# SCH_SPEAR.net
KiCad netlist of a schematic drawn in EasyEDA
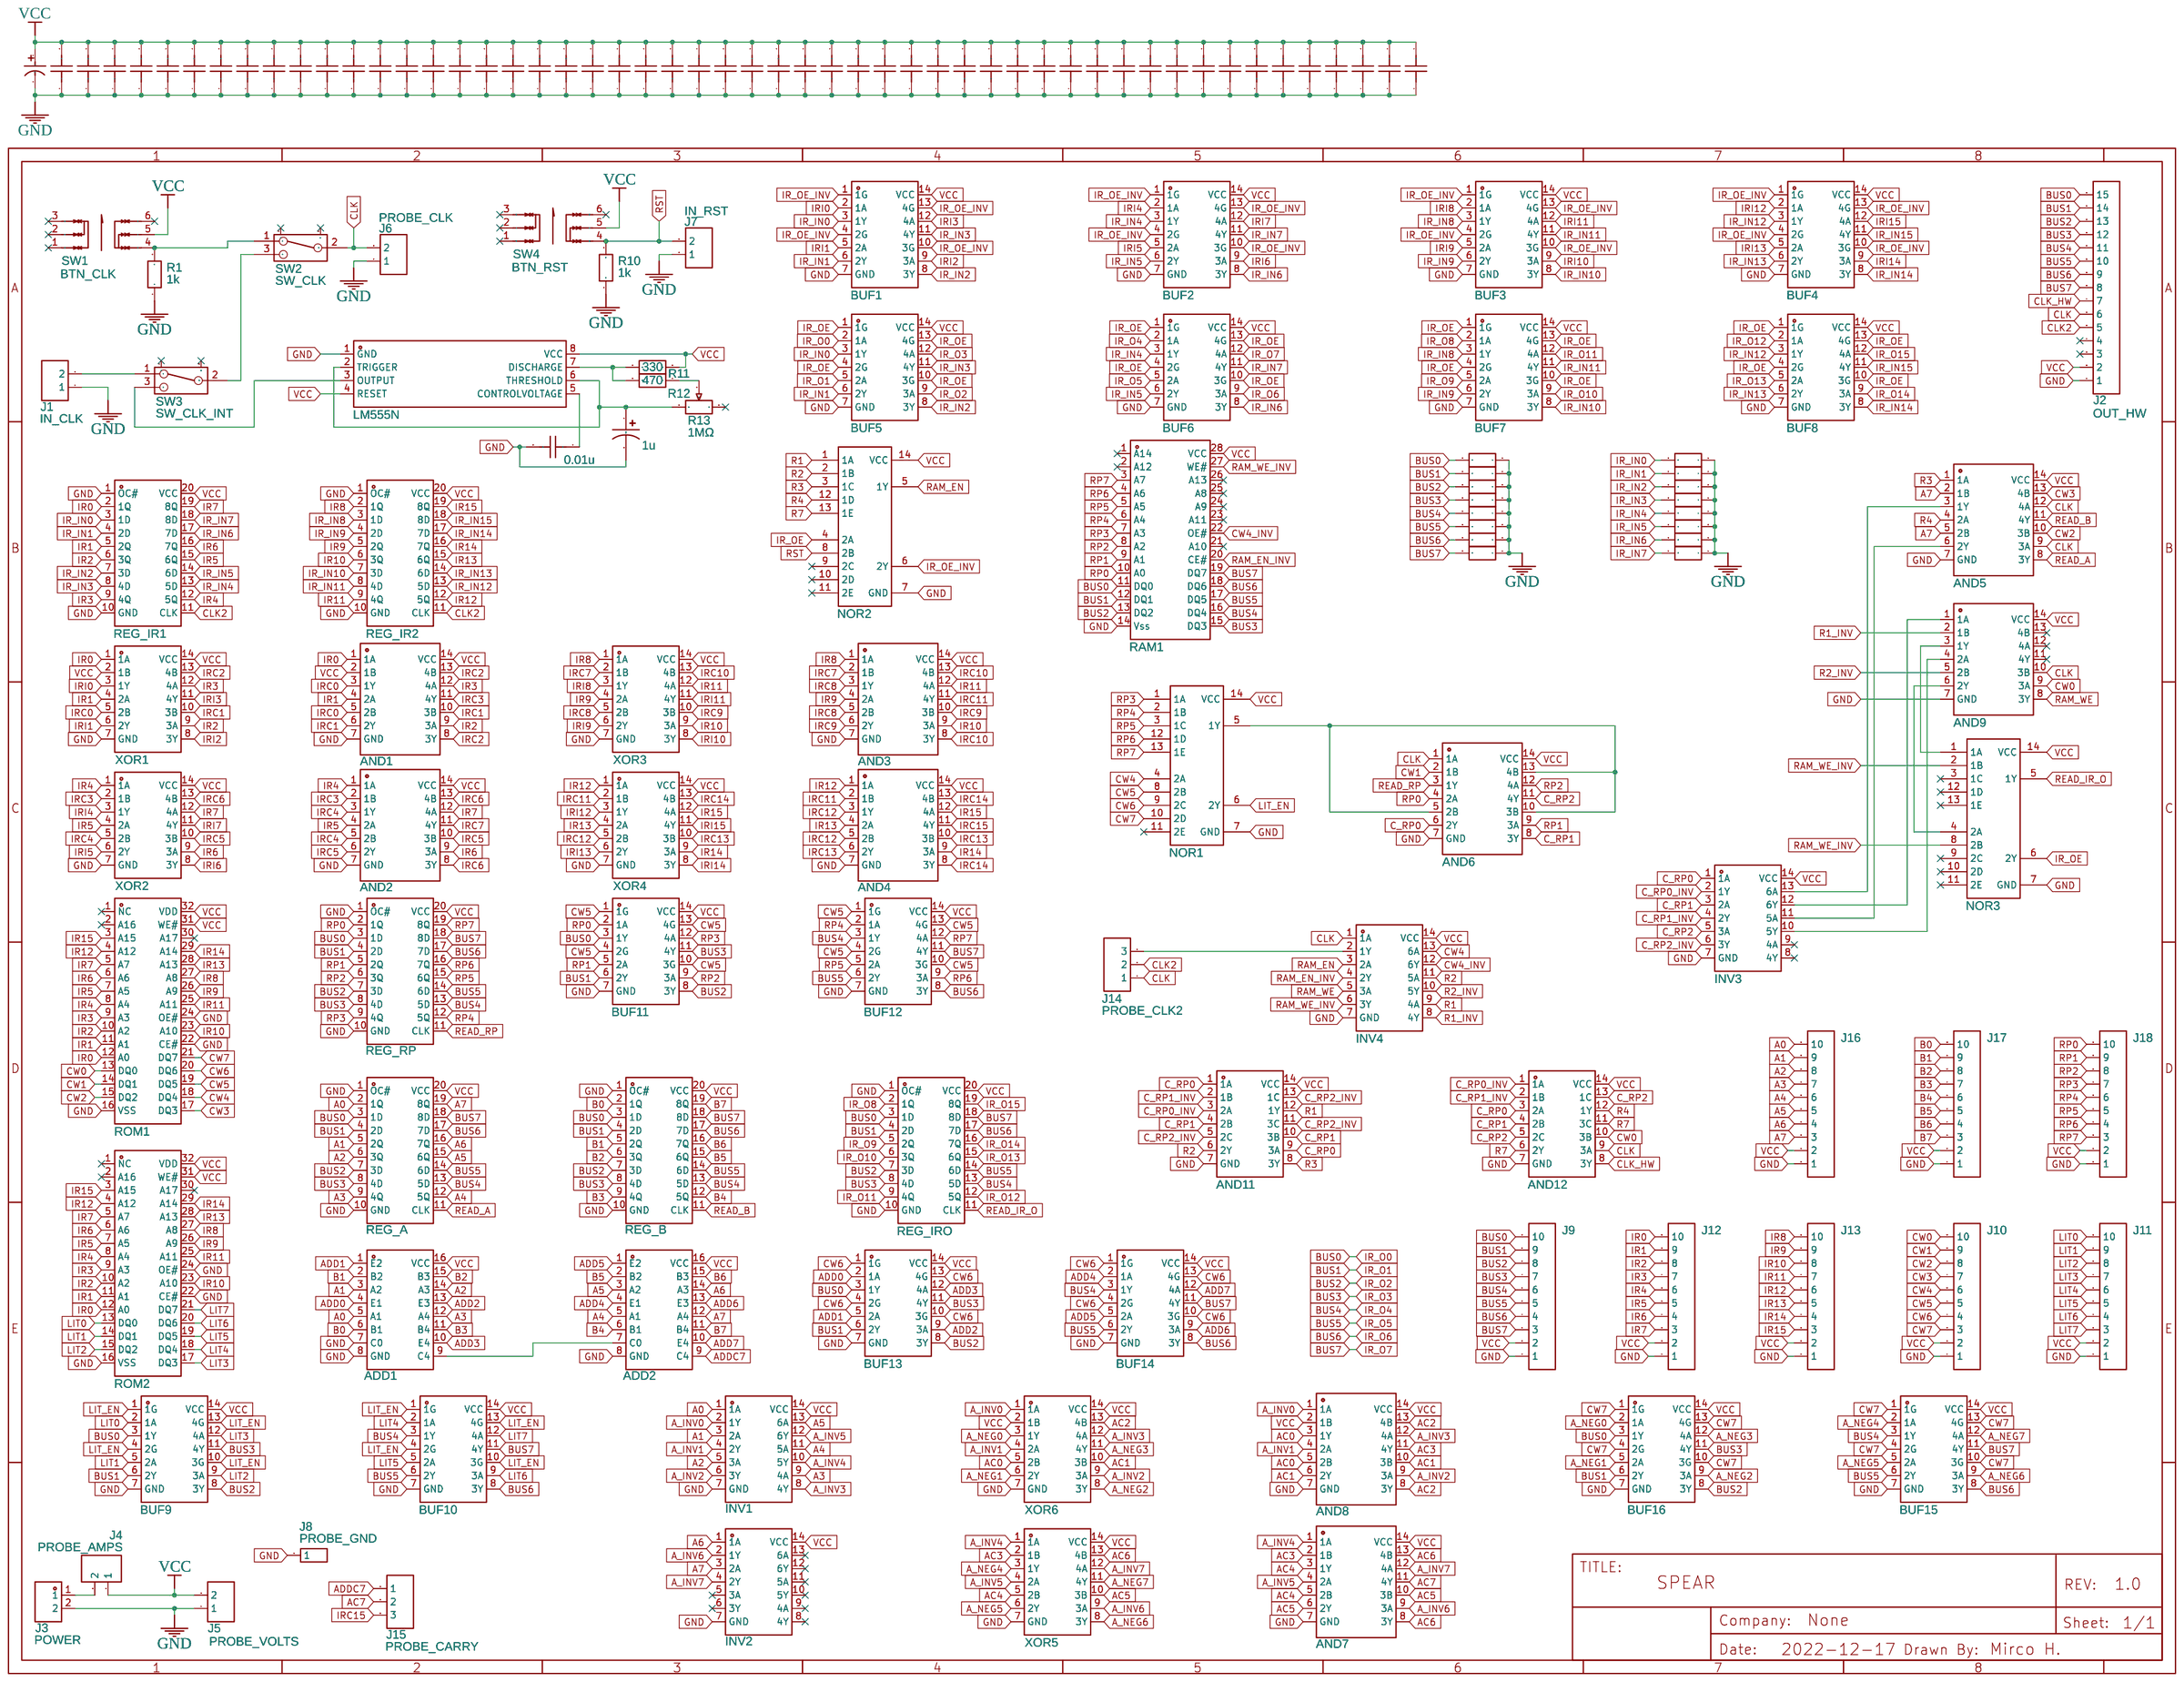
[diagram p0: schematic sheet]

(export (version "E")
  (design (tool "Eeschema 10.0.6"))
  (components
    (comp (ref "ADD1")
      (value "XD74LS283")
      (fields (field (name "BOM_Supplier Part") "C561301"))
      (libsource (lib "") (part "XD74LS283"))
    )
    (comp (ref "ADD2")
      (value "XD74LS283")
      (fields (field (name "BOM_Supplier Part") "C561301"))
      (libsource (lib "") (part "XD74LS283"))
    )
    (comp (ref "AND1")
      (value "SN74LS08DR")
      (fields (field (name "BOM_Supplier Part") "C6802"))
      (libsource (lib "") (part "SN74LS08DR"))
    )
    (comp (ref "AND2")
      (value "SN74LS08DR")
      (fields (field (name "BOM_Supplier Part") "C6802"))
      (libsource (lib "") (part "SN74LS08DR"))
    )
    (comp (ref "AND3")
      (value "SN74LS08DR")
      (fields (field (name "BOM_Supplier Part") "C6802"))
      (libsource (lib "") (part "SN74LS08DR"))
    )
    (comp (ref "AND4")
      (value "SN74LS08DR")
      (fields (field (name "BOM_Supplier Part") "C6802"))
      (libsource (lib "") (part "SN74LS08DR"))
    )
    (comp (ref "AND5")
      (value "SN74LS08DR")
      (fields (field (name "BOM_Supplier Part") "C6802"))
      (libsource (lib "") (part "SN74LS08DR"))
    )
    (comp (ref "AND6")
      (value "SN74LS08DR")
      (fields (field (name "BOM_Supplier Part") "C6802"))
      (libsource (lib "") (part "SN74LS08DR"))
    )
    (comp (ref "AND7")
      (value "SN74LS08DR")
      (fields (field (name "BOM_Supplier Part") "C6802"))
      (libsource (lib "") (part "SN74LS08DR"))
    )
    (comp (ref "AND8")
      (value "SN74LS08DR")
      (fields (field (name "BOM_Supplier Part") "C6802"))
      (libsource (lib "") (part "SN74LS08DR"))
    )
    (comp (ref "AND9")
      (value "SN74LS08DR")
      (fields (field (name "BOM_Supplier Part") "C6802"))
      (libsource (lib "") (part "SN74LS08DR"))
    )
    (comp (ref "AND11")
      (value "XL74LS11")
      (fields (field (name "BOM_Supplier Part") "C521168"))
      (libsource (lib "") (part "XL74LS11"))
    )
    (comp (ref "AND12")
      (value "XL74LS11")
      (fields (field (name "BOM_Supplier Part") "C521168"))
      (libsource (lib "") (part "XL74LS11"))
    )
    (comp (ref "BUF1")
      (value "SN74LS126ADR")
      (fields (field (name "BOM_Supplier Part") "C2865257"))
      (libsource (lib "") (part "SN74LS126ADR"))
    )
    (comp (ref "BUF2")
      (value "SN74LS126ADR")
      (fields (field (name "BOM_Supplier Part") "C2865257"))
      (libsource (lib "") (part "SN74LS126ADR"))
    )
    (comp (ref "BUF3")
      (value "SN74LS126ADR")
      (fields (field (name "BOM_Supplier Part") "C2865257"))
      (libsource (lib "") (part "SN74LS126ADR"))
    )
    (comp (ref "BUF4")
      (value "SN74LS126ADR")
      (fields (field (name "BOM_Supplier Part") "C2865257"))
      (libsource (lib "") (part "SN74LS126ADR"))
    )
    (comp (ref "BUF5")
      (value "SN74LS126ADR")
      (fields (field (name "BOM_Supplier Part") "C2865257"))
      (libsource (lib "") (part "SN74LS126ADR"))
    )
    (comp (ref "BUF6")
      (value "SN74LS126ADR")
      (fields (field (name "BOM_Supplier Part") "C2865257"))
      (libsource (lib "") (part "SN74LS126ADR"))
    )
    (comp (ref "BUF7")
      (value "SN74LS126ADR")
      (fields (field (name "BOM_Supplier Part") "C2865257"))
      (libsource (lib "") (part "SN74LS126ADR"))
    )
    (comp (ref "BUF8")
      (value "SN74LS126ADR")
      (fields (field (name "BOM_Supplier Part") "C2865257"))
      (libsource (lib "") (part "SN74LS126ADR"))
    )
    (comp (ref "BUF9")
      (value "SN74LS126ADR")
      (fields (field (name "BOM_Supplier Part") "C2865257"))
      (libsource (lib "") (part "SN74LS126ADR"))
    )
    (comp (ref "BUF10")
      (value "SN74LS126ADR")
      (fields (field (name "BOM_Supplier Part") "C2865257"))
      (libsource (lib "") (part "SN74LS126ADR"))
    )
    (comp (ref "BUF11")
      (value "SN74LS126ADR")
      (fields (field (name "BOM_Supplier Part") "C2865257"))
      (libsource (lib "") (part "SN74LS126ADR"))
    )
    (comp (ref "BUF12")
      (value "SN74LS126ADR")
      (fields (field (name "BOM_Supplier Part") "C2865257"))
      (libsource (lib "") (part "SN74LS126ADR"))
    )
    (comp (ref "BUF13")
      (value "SN74LS126ADR")
      (fields (field (name "BOM_Supplier Part") "C2865257"))
      (libsource (lib "") (part "SN74LS126ADR"))
    )
    (comp (ref "BUF14")
      (value "SN74LS126ADR")
      (fields (field (name "BOM_Supplier Part") "C2865257"))
      (libsource (lib "") (part "SN74LS126ADR"))
    )
    (comp (ref "BUF15")
      (value "SN74LS126ADR")
      (fields (field (name "BOM_Supplier Part") "C2865257"))
      (libsource (lib "") (part "SN74LS126ADR"))
    )
    (comp (ref "BUF16")
      (value "SN74LS126ADR")
      (fields (field (name "BOM_Supplier Part") "C2865257"))
      (libsource (lib "") (part "SN74LS126ADR"))
    )
    (comp (ref "C1") (value "0.1u") (libsource (lib "") (part "C_0603_US")))
    (comp (ref "C2") (value "0.01u") (libsource (lib "") (part "C_0603_US_1")))
    (comp (ref "C3") (value "1u") (libsource (lib "") (part "C_Tan_SMD_A_US")))
    (comp (ref "C4") (value "0.1u") (libsource (lib "") (part "C_0603_US")))
    (comp (ref "C5") (value "0.1u") (libsource (lib "") (part "C_0603_US")))
    (comp (ref "C6") (value "0.1u") (libsource (lib "") (part "C_0603_US")))
    (comp (ref "C7") (value "0.1u") (libsource (lib "") (part "C_0603_US")))
    (comp (ref "C8") (value "0.1u") (libsource (lib "") (part "C_0603_US")))
    (comp (ref "C9") (value "0.1u") (libsource (lib "") (part "C_0603_US")))
    (comp (ref "C10") (value "0.1u") (libsource (lib "") (part "C_0603_US")))
    (comp (ref "C11") (value "0.1u") (libsource (lib "") (part "C_0603_US")))
    (comp (ref "C12") (value "0.1u") (libsource (lib "") (part "C_0603_US")))
    (comp (ref "C13") (value "0.1u") (libsource (lib "") (part "C_0603_US")))
    (comp (ref "C14") (value "0.1u") (libsource (lib "") (part "C_0603_US")))
    (comp (ref "C15")
      (value "1000uF")
      (fields
        (field (name "BOM_Manufacturer Part") "KM108M025G17RR0VH2FP0")
        (field (name "BOM_Supplier Part") "C10750")
      )
      (libsource (lib "") (part "1000uF 25V"))
    )
    (comp (ref "C58") (value "0.1u") (libsource (lib "") (part "C_0603_US")))
    (comp (ref "C59") (value "0.1u") (libsource (lib "") (part "C_0603_US")))
    (comp (ref "C60") (value "0.1u") (libsource (lib "") (part "C_0603_US")))
    (comp (ref "C61") (value "0.1u") (libsource (lib "") (part "C_0603_US")))
    (comp (ref "C62") (value "0.1u") (libsource (lib "") (part "C_0603_US")))
    (comp (ref "C63") (value "0.1u") (libsource (lib "") (part "C_0603_US")))
    (comp (ref "C64") (value "0.1u") (libsource (lib "") (part "C_0603_US")))
    (comp (ref "C70") (value "0.1u") (libsource (lib "") (part "C_0603_US")))
    (comp (ref "C71") (value "0.1u") (libsource (lib "") (part "C_0603_US")))
    (comp (ref "C72") (value "0.1u") (libsource (lib "") (part "C_0603_US")))
    (comp (ref "C73") (value "0.1u") (libsource (lib "") (part "C_0603_US")))
    (comp (ref "C74") (value "0.1u") (libsource (lib "") (part "C_0603_US")))
    (comp (ref "C75") (value "0.1u") (libsource (lib "") (part "C_0603_US")))
    (comp (ref "C76") (value "0.1u") (libsource (lib "") (part "C_0603_US")))
    (comp (ref "C77") (value "0.1u") (libsource (lib "") (part "C_0603_US")))
    (comp (ref "C78") (value "0.1u") (libsource (lib "") (part "C_0603_US")))
    (comp (ref "C79") (value "0.1u") (libsource (lib "") (part "C_0603_US")))
    (comp (ref "C85") (value "0.1u") (libsource (lib "") (part "C_0603_US")))
    (comp (ref "C86") (value "0.1u") (libsource (lib "") (part "C_0603_US")))
    (comp (ref "C87") (value "0.1u") (libsource (lib "") (part "C_0603_US")))
    (comp (ref "C88") (value "0.1u") (libsource (lib "") (part "C_0603_US")))
    (comp (ref "C89") (value "0.1u") (libsource (lib "") (part "C_0603_US")))
    (comp (ref "C90") (value "0.1u") (libsource (lib "") (part "C_0603_US")))
    (comp (ref "C91") (value "0.1u") (libsource (lib "") (part "C_0603_US")))
    (comp (ref "C92") (value "0.1u") (libsource (lib "") (part "C_0603_US")))
    (comp (ref "C93") (value "0.1u") (libsource (lib "") (part "C_0603_US")))
    (comp (ref "C94") (value "0.1u") (libsource (lib "") (part "C_0603_US")))
    (comp (ref "C95") (value "0.1u") (libsource (lib "") (part "C_0603_US")))
    (comp (ref "C96") (value "0.1u") (libsource (lib "") (part "C_0603_US")))
    (comp (ref "C102") (value "0.1u") (libsource (lib "") (part "C_0603_US")))
    (comp (ref "C103") (value "0.1u") (libsource (lib "") (part "C_0603_US")))
    (comp (ref "C104") (value "0.1u") (libsource (lib "") (part "C_0603_US")))
    (comp (ref "C105") (value "0.1u") (libsource (lib "") (part "C_0603_US")))
    (comp (ref "C106") (value "0.1u") (libsource (lib "") (part "C_0603_US")))
    (comp (ref "C107") (value "0.1u") (libsource (lib "") (part "C_0603_US")))
    (comp (ref "C108") (value "0.1u") (libsource (lib "") (part "C_0603_US")))
    (comp (ref "C109") (value "0.1u") (libsource (lib "") (part "C_0603_US")))
    (comp (ref "C110") (value "0.1u") (libsource (lib "") (part "C_0603_US")))
    (comp (ref "C111") (value "0.1u") (libsource (lib "") (part "C_0603_US")))
    (comp (ref "C112") (value "0.1u") (libsource (lib "") (part "C_0603_US")))
    (comp (ref "INV1")
      (value "XL74LS04")
      (fields (field (name "BOM_Supplier Part") "C513511"))
      (libsource (lib "") (part "XL74LS04"))
    )
    (comp (ref "INV2")
      (value "XL74LS04")
      (fields (field (name "BOM_Supplier Part") "C513511"))
      (libsource (lib "") (part "XL74LS04"))
    )
    (comp (ref "INV3")
      (value "XL74LS04")
      (fields (field (name "BOM_Supplier Part") "C513511"))
      (libsource (lib "") (part "XL74LS04"))
    )
    (comp (ref "INV4")
      (value "XL74LS04")
      (fields (field (name "BOM_Supplier Part") "C513511"))
      (libsource (lib "") (part "XL74LS04"))
    )
    (comp (ref "J1")
      (value "IN_CLK")
      (fields (field (name "BOM_Supplier Part") "C124375"))
      (libsource (lib "") (part "HDR-M-2.54_1x2_2"))
    )
    (comp (ref "J2")
      (value "OUT_HW")
      (fields (field (name "BOM_Supplier Part") "C124373"))
      (libsource (lib "") (part "HDR-M-2.54_1x15"))
    )
    (comp (ref "J3")
      (value "POWER")
      (fields
        (field (name "BOM_Manufacturer Part") "DB126V-5.0-2P-GN-P")
        (field (name "BOM_Supplier Part") "C395849")
      )
      (libsource (lib "") (part "DB126V-5.0-2P"))
    )
    (comp (ref "J4")
      (value "PROBE_AMPS")
      (fields (field (name "BOM_Supplier Part") "C124375"))
      (libsource (lib "") (part "HDR-M-2.54_1x2_1"))
    )
    (comp (ref "J5")
      (value "PROBE_VOLTS")
      (fields (field (name "BOM_Supplier Part") "C124375"))
      (libsource (lib "") (part "HDR-M-2.54_1x2"))
    )
    (comp (ref "J6")
      (value "PROBE_CLK")
      (fields (field (name "BOM_Supplier Part") "C124375"))
      (libsource (lib "") (part "HDR-M-2.54_1x2"))
    )
    (comp (ref "J7")
      (value "IN_RST")
      (fields (field (name "BOM_Supplier Part") "C124375"))
      (libsource (lib "") (part "HDR-M-2.54_1x2"))
    )
    (comp (ref "J8")
      (value "PROBE_GND")
      (fields (field (name "BOM_Supplier Part") "C81276"))
      (libsource (lib "") (part "HDR-M-2.54_1x1"))
    )
    (comp (ref "J9")
      (value "PROBE_BUS")
      (fields (field (name "BOM_Supplier Part") "C57369"))
      (libsource (lib "") (part "HDR-M-2.54_1x10"))
    )
    (comp (ref "J10")
      (value "PROBE_CW")
      (fields (field (name "BOM_Supplier Part") "C57369"))
      (libsource (lib "") (part "HDR-M-2.54_1x10"))
    )
    (comp (ref "J11")
      (value "PROBE_LIT")
      (fields (field (name "BOM_Supplier Part") "C57369"))
      (libsource (lib "") (part "HDR-M-2.54_1x10"))
    )
    (comp (ref "J12")
      (value "PROBE_IR1")
      (fields (field (name "BOM_Supplier Part") "C57369"))
      (libsource (lib "") (part "HDR-M-2.54_1x10"))
    )
    (comp (ref "J13")
      (value "PROBE_IR2")
      (fields (field (name "BOM_Supplier Part") "C57369"))
      (libsource (lib "") (part "HDR-M-2.54_1x10"))
    )
    (comp (ref "J14")
      (value "PROBE_CLK2")
      (fields (field (name "BOM_Supplier Part") "C180248"))
      (libsource (lib "") (part "HDR-M-2.54_1x3"))
    )
    (comp (ref "J15")
      (value "PROBE_CARRY")
      (fields (field (name "BOM_Supplier Part") "C180248"))
      (libsource (lib "") (part "HDR-M-2.54_1x3_1"))
    )
    (comp (ref "J16")
      (value "PROBE_A")
      (fields (field (name "BOM_Supplier Part") "C57369"))
      (libsource (lib "") (part "HDR-M-2.54_1x10"))
    )
    (comp (ref "J17")
      (value "PROBE_B")
      (fields (field (name "BOM_Supplier Part") "C57369"))
      (libsource (lib "") (part "HDR-M-2.54_1x10"))
    )
    (comp (ref "J18")
      (value "PROBE_RP")
      (fields (field (name "BOM_Supplier Part") "C57369"))
      (libsource (lib "") (part "HDR-M-2.54_1x10"))
    )
    (comp (ref "NOR1") (value "LISA_CPU_74LS260") (libsource (lib "") (part "LISA_CPU_74LS260")))
    (comp (ref "NOR2") (value "LISA_CPU_74LS260") (libsource (lib "") (part "LISA_CPU_74LS260")))
    (comp (ref "NOR3") (value "LISA_CPU_74LS260") (libsource (lib "") (part "LISA_CPU_74LS260")))
    (comp (ref "R1") (value "1k") (libsource (lib "") (part "R_0603_EU_1")))
    (comp (ref "R2") (value "10k") (libsource (lib "") (part "R_0603_EU")))
    (comp (ref "R3") (value "10k") (libsource (lib "") (part "R_0603_EU")))
    (comp (ref "R4") (value "10k") (libsource (lib "") (part "R_0603_EU")))
    (comp (ref "R5") (value "10k") (libsource (lib "") (part "R_0603_EU")))
    (comp (ref "R6") (value "10k") (libsource (lib "") (part "R_0603_EU")))
    (comp (ref "R7") (value "10k") (libsource (lib "") (part "R_0603_EU")))
    (comp (ref "R8") (value "10k") (libsource (lib "") (part "R_0603_EU")))
    (comp (ref "R9") (value "10k") (libsource (lib "") (part "R_0603_EU")))
    (comp (ref "R10") (value "1k") (libsource (lib "") (part "R_0603_EU_1")))
    (comp (ref "R11") (value "330") (libsource (lib "") (part "R_0603_EU")))
    (comp (ref "R12") (value "470") (libsource (lib "") (part "R_0603_EU")))
    (comp (ref "R13")
      (value "1MΩ")
      (fields
        (field (name "BOM_Manufacturer Part") "3362P-1-105")
        (field (name "BOM_Supplier Part") "C118945")
      )
      (libsource (lib "") (part "3362P-1-105_C118945"))
    )
    (comp (ref "R14") (value "10k") (libsource (lib "") (part "R_0603_EU")))
    (comp (ref "R15") (value "10k") (libsource (lib "") (part "R_0603_EU")))
    (comp (ref "R16") (value "10k") (libsource (lib "") (part "R_0603_EU")))
    (comp (ref "R17") (value "10k") (libsource (lib "") (part "R_0603_EU")))
    (comp (ref "R18") (value "10k") (libsource (lib "") (part "R_0603_EU")))
    (comp (ref "R19") (value "10k") (libsource (lib "") (part "R_0603_EU")))
    (comp (ref "R20") (value "10k") (libsource (lib "") (part "R_0603_EU")))
    (comp (ref "R21") (value "10k") (libsource (lib "") (part "R_0603_EU")))
    (comp (ref "RAM1")
      (value "LY62256SL-70LL")
      (fields (field (name "BOM_Supplier Part") "C261867"))
      (libsource (lib "") (part "LY62256SL-70LL"))
    )
    (comp (ref "REG1")
      (value "REG_IR1")
      (fields
        (field (name "BOM_Manufacturer Part") "SN74LS374NSR")
        (field (name "BOM_Supplier Part") "C7764")
      )
      (libsource (lib "") (part "SN74LS374NSR"))
    )
    (comp (ref "REG2")
      (value "REG_IR2")
      (fields
        (field (name "BOM_Manufacturer Part") "SN74LS374NSR")
        (field (name "BOM_Supplier Part") "C7764")
      )
      (libsource (lib "") (part "SN74LS374NSR"))
    )
    (comp (ref "REG_A")
      (value "SN74LS374NSR")
      (fields (field (name "BOM_Supplier Part") "C7764"))
      (libsource (lib "") (part "SN74LS374NSR_2"))
    )
    (comp (ref "REG_B")
      (value "SN74LS374NSR")
      (fields (field (name "BOM_Supplier Part") "C7764"))
      (libsource (lib "") (part "SN74LS374NSR_4"))
    )
    (comp (ref "REG_IRO")
      (value "SN74LS374NSR")
      (fields (field (name "BOM_Supplier Part") "C7764"))
      (libsource (lib "") (part "SN74LS374NSR_1"))
    )
    (comp (ref "REG_RP")
      (value "SN74LS374NSR")
      (fields (field (name "BOM_Supplier Part") "C7764"))
      (libsource (lib "") (part "SN74LS374NSR_3"))
    )
    (comp (ref "ROM1")
      (value "SST39SF020A-70-4I-NHE")
      (fields (field (name "BOM_Supplier Part") "C645934"))
      (libsource (lib "") (part "SST39SF020A-70-4I-NHE"))
    )
    (comp (ref "ROM2")
      (value "SST39SF020A-70-4I-NHE")
      (fields (field (name "BOM_Supplier Part") "C645934"))
      (libsource (lib "") (part "SST39SF020A-70-4I-NHE"))
    )
    (comp (ref "SW1")
      (value "BTN_CLK")
      (fields (field (name "BOM_Manufacturer Part") "XKB8080-W") (field (name "BOM_Supplier Part") "C318861"))
      (libsource (lib "") (part "XKB8080-W"))
    )
    (comp (ref "SW2")
      (value "SW_CLK")
      (fields
        (field (name "BOM_Manufacturer Part") "SK-12E12-G5")
        (field (name "BOM_Supplier Part") "C136720")
      )
      (libsource (lib "") (part "SK-12E12-G5"))
    )
    (comp (ref "SW3")
      (value "SW_CLK_INT")
      (fields
        (field (name "BOM_Manufacturer Part") "SK-12E12-G5")
        (field (name "BOM_Supplier Part") "C136720")
      )
      (libsource (lib "") (part "SK-12E12-G5"))
    )
    (comp (ref "SW4")
      (value "BTN_RST")
      (fields (field (name "BOM_Manufacturer Part") "XKB8080-W") (field (name "BOM_Supplier Part") "C318861"))
      (libsource (lib "") (part "XKB8080-W"))
    )
    (comp (ref "U1")
      (value "LM555N")
      (fields (field (name "BOM_Supplier Part") "C725327"))
      (libsource (lib "") (part "LM555N"))
    )
    (comp (ref "XOR1")
      (value "XD74LS86")
      (fields (field (name "BOM_Supplier Part") "C556290"))
      (libsource (lib "") (part "XD74LS86"))
    )
    (comp (ref "XOR2")
      (value "XD74LS86")
      (fields (field (name "BOM_Supplier Part") "C556290"))
      (libsource (lib "") (part "XD74LS86"))
    )
    (comp (ref "XOR3")
      (value "XD74LS86")
      (fields (field (name "BOM_Supplier Part") "C556290"))
      (libsource (lib "") (part "XD74LS86"))
    )
    (comp (ref "XOR4")
      (value "XD74LS86")
      (fields (field (name "BOM_Supplier Part") "C556290"))
      (libsource (lib "") (part "XD74LS86"))
    )
    (comp (ref "XOR5")
      (value "XD74LS86")
      (fields (field (name "BOM_Supplier Part") "C556290"))
      (libsource (lib "") (part "XD74LS86"))
    )
    (comp (ref "XOR6")
      (value "XD74LS86")
      (fields (field (name "BOM_Supplier Part") "C556290"))
      (libsource (lib "") (part "XD74LS86"))
    )
  )
  (nets
    (net (code "1") (name "A0") (class "Default")
      (node (ref "ADD1") (pin "5") (pinfunction "A1_5") (pintype "unspecified"))
      (node (ref "INV1") (pin "1") (pinfunction "1A_1") (pintype "unspecified"))
      (node (ref "J16") (pin "10") (pinfunction "10_10") (pintype "unspecified"))
      (node (ref "REG_A") (pin "2") (pinfunction "1Q_2") (pintype "unspecified"))
    )
    (net (code "2") (name "A1") (class "Default")
      (node (ref "ADD1") (pin "3") (pinfunction "A2_3") (pintype "unspecified"))
      (node (ref "INV1") (pin "3") (pinfunction "2A_3") (pintype "unspecified"))
      (node (ref "J16") (pin "9") (pinfunction "9_9") (pintype "unspecified"))
      (node (ref "REG_A") (pin "5") (pinfunction "2Q_5") (pintype "unspecified"))
    )
    (net (code "3") (name "A2") (class "Default")
      (node (ref "ADD1") (pin "14") (pinfunction "A3_14") (pintype "unspecified"))
      (node (ref "INV1") (pin "5") (pinfunction "3A_5") (pintype "unspecified"))
      (node (ref "J16") (pin "8") (pinfunction "8_8") (pintype "unspecified"))
      (node (ref "REG_A") (pin "6") (pinfunction "3Q_6") (pintype "unspecified"))
    )
    (net (code "4") (name "A3") (class "Default")
      (node (ref "ADD1") (pin "12") (pinfunction "A4_12") (pintype "unspecified"))
      (node (ref "INV1") (pin "9") (pinfunction "4A_9") (pintype "unspecified"))
      (node (ref "J16") (pin "7") (pinfunction "7_7") (pintype "unspecified"))
      (node (ref "REG_A") (pin "9") (pinfunction "4Q_9") (pintype "unspecified"))
    )
    (net (code "5") (name "A4") (class "Default")
      (node (ref "ADD2") (pin "5") (pinfunction "A1_5") (pintype "unspecified"))
      (node (ref "INV1") (pin "11") (pinfunction "5A_11") (pintype "unspecified"))
      (node (ref "J16") (pin "6") (pinfunction "6_6") (pintype "unspecified"))
      (node (ref "REG_A") (pin "12") (pinfunction "5Q_12") (pintype "unspecified"))
    )
    (net (code "6") (name "A5") (class "Default")
      (node (ref "ADD2") (pin "3") (pinfunction "A2_3") (pintype "unspecified"))
      (node (ref "INV1") (pin "13") (pinfunction "6A_13") (pintype "unspecified"))
      (node (ref "J16") (pin "5") (pinfunction "5_5") (pintype "unspecified"))
      (node (ref "REG_A") (pin "15") (pinfunction "6Q_15") (pintype "unspecified"))
    )
    (net (code "7") (name "A6") (class "Default")
      (node (ref "ADD2") (pin "14") (pinfunction "A3_14") (pintype "unspecified"))
      (node (ref "INV2") (pin "1") (pinfunction "1A_1") (pintype "unspecified"))
      (node (ref "J16") (pin "4") (pinfunction "4_4") (pintype "unspecified"))
      (node (ref "REG_A") (pin "16") (pinfunction "7Q_16") (pintype "unspecified"))
    )
    (net (code "8") (name "A7") (class "Default")
      (node (ref "ADD2") (pin "12") (pinfunction "A4_12") (pintype "unspecified"))
      (node (ref "AND5") (pin "2") (pinfunction "1B_2") (pintype "unspecified"))
      (node (ref "AND5") (pin "5") (pinfunction "2B_5") (pintype "unspecified"))
      (node (ref "INV2") (pin "3") (pinfunction "2A_3") (pintype "unspecified"))
      (node (ref "J16") (pin "3") (pinfunction "3_3") (pintype "unspecified"))
      (node (ref "REG_A") (pin "19") (pinfunction "8Q_19") (pintype "unspecified"))
    )
    (net (code "9") (name "AC0") (class "Default")
      (node (ref "AND8") (pin "3") (pinfunction "1Y_3") (pintype "unspecified"))
      (node (ref "AND8") (pin "5") (pinfunction "2B_5") (pintype "unspecified"))
      (node (ref "XOR6") (pin "5") (pinfunction "2B_5") (pintype "unspecified"))
    )
    (net (code "10") (name "AC1") (class "Default")
      (node (ref "AND8") (pin "10") (pinfunction "3B_10") (pintype "unspecified"))
      (node (ref "AND8") (pin "6") (pinfunction "2Y_6") (pintype "unspecified"))
      (node (ref "XOR6") (pin "10") (pinfunction "3B_10") (pintype "unspecified"))
    )
    (net (code "11") (name "AC2") (class "Default")
      (node (ref "AND8") (pin "13") (pinfunction "4B_13") (pintype "unspecified"))
      (node (ref "AND8") (pin "8") (pinfunction "3Y_8") (pintype "unspecified"))
      (node (ref "XOR6") (pin "13") (pinfunction "4B_13") (pintype "unspecified"))
    )
    (net (code "12") (name "AC3") (class "Default")
      (node (ref "AND7") (pin "2") (pinfunction "1B_2") (pintype "unspecified"))
      (node (ref "AND8") (pin "11") (pinfunction "4Y_11") (pintype "unspecified"))
      (node (ref "XOR5") (pin "2") (pinfunction "1B_2") (pintype "unspecified"))
    )
    (net (code "13") (name "AC4") (class "Default")
      (node (ref "AND7") (pin "3") (pinfunction "1Y_3") (pintype "unspecified"))
      (node (ref "AND7") (pin "5") (pinfunction "2B_5") (pintype "unspecified"))
      (node (ref "XOR5") (pin "5") (pinfunction "2B_5") (pintype "unspecified"))
    )
    (net (code "14") (name "AC5") (class "Default")
      (node (ref "AND7") (pin "10") (pinfunction "3B_10") (pintype "unspecified"))
      (node (ref "AND7") (pin "6") (pinfunction "2Y_6") (pintype "unspecified"))
      (node (ref "XOR5") (pin "10") (pinfunction "3B_10") (pintype "unspecified"))
    )
    (net (code "15") (name "AC6") (class "Default")
      (node (ref "AND7") (pin "13") (pinfunction "4B_13") (pintype "unspecified"))
      (node (ref "AND7") (pin "8") (pinfunction "3Y_8") (pintype "unspecified"))
      (node (ref "XOR5") (pin "13") (pinfunction "4B_13") (pintype "unspecified"))
    )
    (net (code "16") (name "AC7") (class "Default")
      (node (ref "AND7") (pin "11") (pinfunction "4Y_11") (pintype "unspecified"))
      (node (ref "J15") (pin "2") (pinfunction "2_2") (pintype "input"))
    )
    (net (code "17") (name "ADD0") (class "Default")
      (node (ref "ADD1") (pin "4") (pinfunction "E1_4") (pintype "unspecified"))
      (node (ref "BUF13") (pin "2") (pinfunction "1A_2") (pintype "unspecified"))
    )
    (net (code "18") (name "ADD1") (class "Default")
      (node (ref "ADD1") (pin "1") (pinfunction "E2_1") (pintype "unspecified"))
      (node (ref "BUF13") (pin "5") (pinfunction "2A_5") (pintype "unspecified"))
    )
    (net (code "19") (name "ADD2") (class "Default")
      (node (ref "ADD1") (pin "13") (pinfunction "E3_13") (pintype "unspecified"))
      (node (ref "BUF13") (pin "9") (pinfunction "3A_9") (pintype "unspecified"))
    )
    (net (code "20") (name "ADD3") (class "Default")
      (node (ref "ADD1") (pin "10") (pinfunction "E4_10") (pintype "unspecified"))
      (node (ref "BUF13") (pin "12") (pinfunction "4A_12") (pintype "unspecified"))
    )
    (net (code "21") (name "ADD4") (class "Default")
      (node (ref "ADD2") (pin "4") (pinfunction "E1_4") (pintype "unspecified"))
      (node (ref "BUF14") (pin "2") (pinfunction "1A_2") (pintype "unspecified"))
    )
    (net (code "22") (name "ADD5") (class "Default")
      (node (ref "ADD2") (pin "1") (pinfunction "E2_1") (pintype "unspecified"))
      (node (ref "BUF14") (pin "5") (pinfunction "2A_5") (pintype "unspecified"))
    )
    (net (code "23") (name "ADD6") (class "Default")
      (node (ref "ADD2") (pin "13") (pinfunction "E3_13") (pintype "unspecified"))
      (node (ref "BUF14") (pin "9") (pinfunction "3A_9") (pintype "unspecified"))
    )
    (net (code "24") (name "ADD7") (class "Default")
      (node (ref "ADD2") (pin "10") (pinfunction "E4_10") (pintype "unspecified"))
      (node (ref "BUF14") (pin "12") (pinfunction "4A_12") (pintype "unspecified"))
    )
    (net (code "25") (name "ADDC7") (class "Default")
      (node (ref "ADD2") (pin "9") (pinfunction "C4_9") (pintype "unspecified"))
      (node (ref "J15") (pin "1") (pinfunction "1_1") (pintype "input"))
    )
    (net (code "26") (name "A_INV0") (class "Default")
      (node (ref "AND8") (pin "1") (pinfunction "1A_1") (pintype "unspecified"))
      (node (ref "INV1") (pin "2") (pinfunction "1Y_2") (pintype "unspecified"))
      (node (ref "XOR6") (pin "1") (pinfunction "1A_1") (pintype "unspecified"))
    )
    (net (code "27") (name "A_INV1") (class "Default")
      (node (ref "AND8") (pin "4") (pinfunction "2A_4") (pintype "unspecified"))
      (node (ref "INV1") (pin "4") (pinfunction "2Y_4") (pintype "unspecified"))
      (node (ref "XOR6") (pin "4") (pinfunction "2A_4") (pintype "unspecified"))
    )
    (net (code "28") (name "A_INV2") (class "Default")
      (node (ref "AND8") (pin "9") (pinfunction "3A_9") (pintype "unspecified"))
      (node (ref "INV1") (pin "6") (pinfunction "3Y_6") (pintype "unspecified"))
      (node (ref "XOR6") (pin "9") (pinfunction "3A_9") (pintype "unspecified"))
    )
    (net (code "29") (name "A_INV3") (class "Default")
      (node (ref "AND8") (pin "12") (pinfunction "4A_12") (pintype "unspecified"))
      (node (ref "INV1") (pin "8") (pinfunction "4Y_8") (pintype "unspecified"))
      (node (ref "XOR6") (pin "12") (pinfunction "4A_12") (pintype "unspecified"))
    )
    (net (code "30") (name "A_INV4") (class "Default")
      (node (ref "AND7") (pin "1") (pinfunction "1A_1") (pintype "unspecified"))
      (node (ref "INV1") (pin "10") (pinfunction "5Y_10") (pintype "unspecified"))
      (node (ref "XOR5") (pin "1") (pinfunction "1A_1") (pintype "unspecified"))
    )
    (net (code "31") (name "A_INV5") (class "Default")
      (node (ref "AND7") (pin "4") (pinfunction "2A_4") (pintype "unspecified"))
      (node (ref "INV1") (pin "12") (pinfunction "6Y_12") (pintype "unspecified"))
      (node (ref "XOR5") (pin "4") (pinfunction "2A_4") (pintype "unspecified"))
    )
    (net (code "32") (name "A_INV6") (class "Default")
      (node (ref "AND7") (pin "9") (pinfunction "3A_9") (pintype "unspecified"))
      (node (ref "INV2") (pin "2") (pinfunction "1Y_2") (pintype "unspecified"))
      (node (ref "XOR5") (pin "9") (pinfunction "3A_9") (pintype "unspecified"))
    )
    (net (code "33") (name "A_INV7") (class "Default")
      (node (ref "AND7") (pin "12") (pinfunction "4A_12") (pintype "unspecified"))
      (node (ref "INV2") (pin "4") (pinfunction "2Y_4") (pintype "unspecified"))
      (node (ref "XOR5") (pin "12") (pinfunction "4A_12") (pintype "unspecified"))
    )
    (net (code "34") (name "A_NEG0") (class "Default")
      (node (ref "BUF16") (pin "2") (pinfunction "1A_2") (pintype "unspecified"))
      (node (ref "XOR6") (pin "3") (pinfunction "1Y_3") (pintype "unspecified"))
    )
    (net (code "35") (name "A_NEG1") (class "Default")
      (node (ref "BUF16") (pin "5") (pinfunction "2A_5") (pintype "unspecified"))
      (node (ref "XOR6") (pin "6") (pinfunction "2Y_6") (pintype "unspecified"))
    )
    (net (code "36") (name "A_NEG2") (class "Default")
      (node (ref "BUF16") (pin "9") (pinfunction "3A_9") (pintype "unspecified"))
      (node (ref "XOR6") (pin "8") (pinfunction "3Y_8") (pintype "unspecified"))
    )
    (net (code "37") (name "A_NEG3") (class "Default")
      (node (ref "BUF16") (pin "12") (pinfunction "4A_12") (pintype "unspecified"))
      (node (ref "XOR6") (pin "11") (pinfunction "4Y_11") (pintype "unspecified"))
    )
    (net (code "38") (name "A_NEG4") (class "Default")
      (node (ref "BUF15") (pin "2") (pinfunction "1A_2") (pintype "unspecified"))
      (node (ref "XOR5") (pin "3") (pinfunction "1Y_3") (pintype "unspecified"))
    )
    (net (code "39") (name "A_NEG5") (class "Default")
      (node (ref "BUF15") (pin "5") (pinfunction "2A_5") (pintype "unspecified"))
      (node (ref "XOR5") (pin "6") (pinfunction "2Y_6") (pintype "unspecified"))
    )
    (net (code "40") (name "A_NEG6") (class "Default")
      (node (ref "BUF15") (pin "9") (pinfunction "3A_9") (pintype "unspecified"))
      (node (ref "XOR5") (pin "8") (pinfunction "3Y_8") (pintype "unspecified"))
    )
    (net (code "41") (name "A_NEG7") (class "Default")
      (node (ref "BUF15") (pin "12") (pinfunction "4A_12") (pintype "unspecified"))
      (node (ref "XOR5") (pin "11") (pinfunction "4Y_11") (pintype "unspecified"))
    )
    (net (code "42") (name "B0") (class "Default")
      (node (ref "ADD1") (pin "6") (pinfunction "B1_6") (pintype "unspecified"))
      (node (ref "J17") (pin "10") (pinfunction "10_10") (pintype "unspecified"))
      (node (ref "REG_B") (pin "2") (pinfunction "1Q_2") (pintype "unspecified"))
    )
    (net (code "43") (name "B1") (class "Default")
      (node (ref "ADD1") (pin "2") (pinfunction "B2_2") (pintype "unspecified"))
      (node (ref "J17") (pin "9") (pinfunction "9_9") (pintype "unspecified"))
      (node (ref "REG_B") (pin "5") (pinfunction "2Q_5") (pintype "unspecified"))
    )
    (net (code "44") (name "B2") (class "Default")
      (node (ref "ADD1") (pin "15") (pinfunction "B3_15") (pintype "unspecified"))
      (node (ref "J17") (pin "8") (pinfunction "8_8") (pintype "unspecified"))
      (node (ref "REG_B") (pin "6") (pinfunction "3Q_6") (pintype "unspecified"))
    )
    (net (code "45") (name "B3") (class "Default")
      (node (ref "ADD1") (pin "11") (pinfunction "B4_11") (pintype "unspecified"))
      (node (ref "J17") (pin "7") (pinfunction "7_7") (pintype "unspecified"))
      (node (ref "REG_B") (pin "9") (pinfunction "4Q_9") (pintype "unspecified"))
    )
    (net (code "46") (name "B4") (class "Default")
      (node (ref "ADD2") (pin "6") (pinfunction "B1_6") (pintype "unspecified"))
      (node (ref "J17") (pin "6") (pinfunction "6_6") (pintype "unspecified"))
      (node (ref "REG_B") (pin "12") (pinfunction "5Q_12") (pintype "unspecified"))
    )
    (net (code "47") (name "B5") (class "Default")
      (node (ref "ADD2") (pin "2") (pinfunction "B2_2") (pintype "unspecified"))
      (node (ref "J17") (pin "5") (pinfunction "5_5") (pintype "unspecified"))
      (node (ref "REG_B") (pin "15") (pinfunction "6Q_15") (pintype "unspecified"))
    )
    (net (code "48") (name "B6") (class "Default")
      (node (ref "ADD2") (pin "15") (pinfunction "B3_15") (pintype "unspecified"))
      (node (ref "J17") (pin "4") (pinfunction "4_4") (pintype "unspecified"))
      (node (ref "REG_B") (pin "16") (pinfunction "7Q_16") (pintype "unspecified"))
    )
    (net (code "49") (name "B7") (class "Default")
      (node (ref "ADD2") (pin "11") (pinfunction "B4_11") (pintype "unspecified"))
      (node (ref "J17") (pin "3") (pinfunction "3_3") (pintype "unspecified"))
      (node (ref "REG_B") (pin "19") (pinfunction "8Q_19") (pintype "unspecified"))
    )
    (net (code "50") (name "BUS0") (class "Default")
      (node (ref "BUF11") (pin "3") (pinfunction "1Y_3") (pintype "unspecified"))
      (node (ref "BUF13") (pin "3") (pinfunction "1Y_3") (pintype "unspecified"))
      (node (ref "BUF16") (pin "3") (pinfunction "1Y_3") (pintype "unspecified"))
      (node (ref "BUF5") (pin "2") (pinfunction "1A_2") (pintype "unspecified"))
      (node (ref "BUF9") (pin "3") (pinfunction "1Y_3") (pintype "unspecified"))
      (node (ref "J2") (pin "15") (pinfunction "15_15") (pintype "unspecified"))
      (node (ref "J9") (pin "10") (pinfunction "10_10") (pintype "unspecified"))
      (node (ref "R14") (pin "2") (pinfunction "2_2") (pintype "unspecified"))
      (node (ref "RAM1") (pin "11") (pinfunction "DQ0_11") (pintype "unspecified"))
      (node (ref "REG_A") (pin "3") (pinfunction "1D_3") (pintype "unspecified"))
      (node (ref "REG_B") (pin "3") (pinfunction "1D_3") (pintype "unspecified"))
      (node (ref "REG_IRO") (pin "3") (pinfunction "1D_3") (pintype "unspecified"))
      (node (ref "REG_RP") (pin "3") (pinfunction "1D_3") (pintype "unspecified"))
    )
    (net (code "51") (name "BUS1") (class "Default")
      (node (ref "BUF11") (pin "6") (pinfunction "2Y_6") (pintype "unspecified"))
      (node (ref "BUF13") (pin "6") (pinfunction "2Y_6") (pintype "unspecified"))
      (node (ref "BUF16") (pin "6") (pinfunction "2Y_6") (pintype "unspecified"))
      (node (ref "BUF5") (pin "5") (pinfunction "2A_5") (pintype "unspecified"))
      (node (ref "BUF9") (pin "6") (pinfunction "2Y_6") (pintype "unspecified"))
      (node (ref "J2") (pin "14") (pinfunction "14_14") (pintype "unspecified"))
      (node (ref "J9") (pin "9") (pinfunction "9_9") (pintype "unspecified"))
      (node (ref "R15") (pin "2") (pinfunction "2_2") (pintype "unspecified"))
      (node (ref "RAM1") (pin "12") (pinfunction "DQ1_12") (pintype "unspecified"))
      (node (ref "REG_A") (pin "4") (pinfunction "2D_4") (pintype "unspecified"))
      (node (ref "REG_B") (pin "4") (pinfunction "2D_4") (pintype "unspecified"))
      (node (ref "REG_IRO") (pin "4") (pinfunction "2D_4") (pintype "unspecified"))
      (node (ref "REG_RP") (pin "4") (pinfunction "2D_4") (pintype "unspecified"))
    )
    (net (code "52") (name "BUS2") (class "Default")
      (node (ref "BUF11") (pin "8") (pinfunction "3Y_8") (pintype "unspecified"))
      (node (ref "BUF13") (pin "8") (pinfunction "3Y_8") (pintype "unspecified"))
      (node (ref "BUF16") (pin "8") (pinfunction "3Y_8") (pintype "unspecified"))
      (node (ref "BUF5") (pin "9") (pinfunction "3A_9") (pintype "unspecified"))
      (node (ref "BUF9") (pin "8") (pinfunction "3Y_8") (pintype "unspecified"))
      (node (ref "J2") (pin "13") (pinfunction "13_13") (pintype "unspecified"))
      (node (ref "J9") (pin "8") (pinfunction "8_8") (pintype "unspecified"))
      (node (ref "R16") (pin "2") (pinfunction "2_2") (pintype "unspecified"))
      (node (ref "RAM1") (pin "13") (pinfunction "DQ2_13") (pintype "unspecified"))
      (node (ref "REG_A") (pin "7") (pinfunction "3D_7") (pintype "unspecified"))
      (node (ref "REG_B") (pin "7") (pinfunction "3D_7") (pintype "unspecified"))
      (node (ref "REG_IRO") (pin "7") (pinfunction "3D_7") (pintype "unspecified"))
      (node (ref "REG_RP") (pin "7") (pinfunction "3D_7") (pintype "unspecified"))
    )
    (net (code "53") (name "BUS3") (class "Default")
      (node (ref "BUF11") (pin "11") (pinfunction "4Y_11") (pintype "unspecified"))
      (node (ref "BUF13") (pin "11") (pinfunction "4Y_11") (pintype "unspecified"))
      (node (ref "BUF16") (pin "11") (pinfunction "4Y_11") (pintype "unspecified"))
      (node (ref "BUF5") (pin "12") (pinfunction "4A_12") (pintype "unspecified"))
      (node (ref "BUF9") (pin "11") (pinfunction "4Y_11") (pintype "unspecified"))
      (node (ref "J2") (pin "12") (pinfunction "12_12") (pintype "unspecified"))
      (node (ref "J9") (pin "7") (pinfunction "7_7") (pintype "unspecified"))
      (node (ref "R17") (pin "2") (pinfunction "2_2") (pintype "unspecified"))
      (node (ref "RAM1") (pin "15") (pinfunction "DQ3_15") (pintype "unspecified"))
      (node (ref "REG_A") (pin "8") (pinfunction "4D_8") (pintype "unspecified"))
      (node (ref "REG_B") (pin "8") (pinfunction "4D_8") (pintype "unspecified"))
      (node (ref "REG_IRO") (pin "8") (pinfunction "4D_8") (pintype "unspecified"))
      (node (ref "REG_RP") (pin "8") (pinfunction "4D_8") (pintype "unspecified"))
    )
    (net (code "54") (name "BUS4") (class "Default")
      (node (ref "BUF10") (pin "3") (pinfunction "1Y_3") (pintype "unspecified"))
      (node (ref "BUF12") (pin "3") (pinfunction "1Y_3") (pintype "unspecified"))
      (node (ref "BUF14") (pin "3") (pinfunction "1Y_3") (pintype "unspecified"))
      (node (ref "BUF15") (pin "3") (pinfunction "1Y_3") (pintype "unspecified"))
      (node (ref "BUF6") (pin "2") (pinfunction "1A_2") (pintype "unspecified"))
      (node (ref "J2") (pin "11") (pinfunction "11_11") (pintype "unspecified"))
      (node (ref "J9") (pin "6") (pinfunction "6_6") (pintype "unspecified"))
      (node (ref "R18") (pin "2") (pinfunction "2_2") (pintype "unspecified"))
      (node (ref "RAM1") (pin "16") (pinfunction "DQ4_16") (pintype "unspecified"))
      (node (ref "REG_A") (pin "13") (pinfunction "5D_13") (pintype "unspecified"))
      (node (ref "REG_B") (pin "13") (pinfunction "5D_13") (pintype "unspecified"))
      (node (ref "REG_IRO") (pin "13") (pinfunction "5D_13") (pintype "unspecified"))
      (node (ref "REG_RP") (pin "13") (pinfunction "5D_13") (pintype "unspecified"))
    )
    (net (code "55") (name "BUS5") (class "Default")
      (node (ref "BUF10") (pin "6") (pinfunction "2Y_6") (pintype "unspecified"))
      (node (ref "BUF12") (pin "6") (pinfunction "2Y_6") (pintype "unspecified"))
      (node (ref "BUF14") (pin "6") (pinfunction "2Y_6") (pintype "unspecified"))
      (node (ref "BUF15") (pin "6") (pinfunction "2Y_6") (pintype "unspecified"))
      (node (ref "BUF6") (pin "5") (pinfunction "2A_5") (pintype "unspecified"))
      (node (ref "J2") (pin "10") (pinfunction "10_10") (pintype "unspecified"))
      (node (ref "J9") (pin "5") (pinfunction "5_5") (pintype "unspecified"))
      (node (ref "R19") (pin "2") (pinfunction "2_2") (pintype "unspecified"))
      (node (ref "RAM1") (pin "17") (pinfunction "DQ5_17") (pintype "unspecified"))
      (node (ref "REG_A") (pin "14") (pinfunction "6D_14") (pintype "unspecified"))
      (node (ref "REG_B") (pin "14") (pinfunction "6D_14") (pintype "unspecified"))
      (node (ref "REG_IRO") (pin "14") (pinfunction "6D_14") (pintype "unspecified"))
      (node (ref "REG_RP") (pin "14") (pinfunction "6D_14") (pintype "unspecified"))
    )
    (net (code "56") (name "BUS6") (class "Default")
      (node (ref "BUF10") (pin "8") (pinfunction "3Y_8") (pintype "unspecified"))
      (node (ref "BUF12") (pin "8") (pinfunction "3Y_8") (pintype "unspecified"))
      (node (ref "BUF14") (pin "8") (pinfunction "3Y_8") (pintype "unspecified"))
      (node (ref "BUF15") (pin "8") (pinfunction "3Y_8") (pintype "unspecified"))
      (node (ref "BUF6") (pin "9") (pinfunction "3A_9") (pintype "unspecified"))
      (node (ref "J2") (pin "9") (pinfunction "9_9") (pintype "unspecified"))
      (node (ref "J9") (pin "4") (pinfunction "4_4") (pintype "unspecified"))
      (node (ref "R20") (pin "2") (pinfunction "2_2") (pintype "unspecified"))
      (node (ref "RAM1") (pin "18") (pinfunction "DQ6_18") (pintype "unspecified"))
      (node (ref "REG_A") (pin "17") (pinfunction "7D_17") (pintype "unspecified"))
      (node (ref "REG_B") (pin "17") (pinfunction "7D_17") (pintype "unspecified"))
      (node (ref "REG_IRO") (pin "17") (pinfunction "7D_17") (pintype "unspecified"))
      (node (ref "REG_RP") (pin "17") (pinfunction "7D_17") (pintype "unspecified"))
    )
    (net (code "57") (name "BUS7") (class "Default")
      (node (ref "BUF10") (pin "11") (pinfunction "4Y_11") (pintype "unspecified"))
      (node (ref "BUF12") (pin "11") (pinfunction "4Y_11") (pintype "unspecified"))
      (node (ref "BUF14") (pin "11") (pinfunction "4Y_11") (pintype "unspecified"))
      (node (ref "BUF15") (pin "11") (pinfunction "4Y_11") (pintype "unspecified"))
      (node (ref "BUF6") (pin "12") (pinfunction "4A_12") (pintype "unspecified"))
      (node (ref "J2") (pin "8") (pinfunction "8_8") (pintype "unspecified"))
      (node (ref "J9") (pin "3") (pinfunction "3_3") (pintype "unspecified"))
      (node (ref "R21") (pin "2") (pinfunction "2_2") (pintype "unspecified"))
      (node (ref "RAM1") (pin "19") (pinfunction "DQ7_19") (pintype "unspecified"))
      (node (ref "REG_A") (pin "18") (pinfunction "8D_18") (pintype "unspecified"))
      (node (ref "REG_B") (pin "18") (pinfunction "8D_18") (pintype "unspecified"))
      (node (ref "REG_IRO") (pin "18") (pinfunction "8D_18") (pintype "unspecified"))
      (node (ref "REG_RP") (pin "18") (pinfunction "8D_18") (pintype "unspecified"))
    )
    (net (code "58") (name "CLK") (class "Default")
      (node (ref "AND12") (pin "9") (pinfunction "3A_9") (pintype "unspecified"))
      (node (ref "AND5") (pin "12") (pinfunction "4A_12") (pintype "unspecified"))
      (node (ref "AND5") (pin "9") (pinfunction "3A_9") (pintype "unspecified"))
      (node (ref "AND6") (pin "1") (pinfunction "1A_1") (pintype "unspecified"))
      (node (ref "AND9") (pin "10") (pinfunction "3B_10") (pintype "unspecified"))
      (node (ref "INV4") (pin "1") (pinfunction "1A_1") (pintype "unspecified"))
      (node (ref "J14") (pin "1") (pinfunction "1_1") (pintype "input"))
      (node (ref "J2") (pin "6") (pinfunction "6_6") (pintype "unspecified"))
      (node (ref "J6") (pin "2") (pinfunction "2_2") (pintype "unspecified"))
      (node (ref "SW2") (pin "2") (pinfunction "2_2") (pintype "unspecified"))
    )
    (net (code "59") (name "CLK2") (class "Default")
      (node (ref "J14") (pin "2") (pinfunction "2_2") (pintype "input"))
      (node (ref "J2") (pin "5") (pinfunction "5_5") (pintype "unspecified"))
      (node (ref "REG1") (pin "11") (pinfunction "CLK_11") (pintype "unspecified"))
      (node (ref "REG2") (pin "11") (pinfunction "CLK_11") (pintype "unspecified"))
    )
    (net (code "60") (name "CLK_HW") (class "Default")
      (node (ref "AND12") (pin "8") (pinfunction "3Y_8") (pintype "unspecified"))
      (node (ref "J2") (pin "7") (pinfunction "7_7") (pintype "unspecified"))
    )
    (net (code "61") (name "CW0") (class "Default")
      (node (ref "AND12") (pin "10") (pinfunction "3B_10") (pintype "unspecified"))
      (node (ref "AND9") (pin "9") (pinfunction "3A_9") (pintype "unspecified"))
      (node (ref "J10") (pin "10") (pinfunction "10_10") (pintype "unspecified"))
      (node (ref "ROM1") (pin "13") (pinfunction "DQ0_13") (pintype "unspecified"))
    )
    (net (code "62") (name "CW1") (class "Default")
      (node (ref "AND6") (pin "2") (pinfunction "1B_2") (pintype "unspecified"))
      (node (ref "J10") (pin "9") (pinfunction "9_9") (pintype "unspecified"))
      (node (ref "ROM1") (pin "14") (pinfunction "DQ1_14") (pintype "unspecified"))
    )
    (net (code "63") (name "CW2") (class "Default")
      (node (ref "AND5") (pin "10") (pinfunction "3B_10") (pintype "unspecified"))
      (node (ref "J10") (pin "8") (pinfunction "8_8") (pintype "unspecified"))
      (node (ref "ROM1") (pin "15") (pinfunction "DQ2_15") (pintype "unspecified"))
    )
    (net (code "64") (name "CW3") (class "Default")
      (node (ref "AND5") (pin "13") (pinfunction "4B_13") (pintype "unspecified"))
      (node (ref "J10") (pin "7") (pinfunction "7_7") (pintype "unspecified"))
      (node (ref "ROM1") (pin "17") (pinfunction "DQ3_17") (pintype "unspecified"))
    )
    (net (code "65") (name "CW4") (class "Default")
      (node (ref "INV4") (pin "13") (pinfunction "6A_13") (pintype "unspecified"))
      (node (ref "J10") (pin "6") (pinfunction "6_6") (pintype "unspecified"))
      (node (ref "NOR1") (pin "4") (pinfunction "2A_4") (pintype "unspecified"))
      (node (ref "ROM1") (pin "18") (pinfunction "DQ4_18") (pintype "unspecified"))
    )
    (net (code "66") (name "CW4_INV") (class "Default")
      (node (ref "INV4") (pin "12") (pinfunction "6Y_12") (pintype "unspecified"))
      (node (ref "RAM1") (pin "22") (pinfunction "OE#_22") (pintype "unspecified"))
    )
    (net (code "67") (name "CW5") (class "Default")
      (node (ref "BUF11") (pin "1") (pinfunction "1G_1") (pintype "unspecified"))
      (node (ref "BUF11") (pin "10") (pinfunction "3G_10") (pintype "unspecified"))
      (node (ref "BUF11") (pin "13") (pinfunction "4G_13") (pintype "unspecified"))
      (node (ref "BUF11") (pin "4") (pinfunction "2G_4") (pintype "unspecified"))
      (node (ref "BUF12") (pin "1") (pinfunction "1G_1") (pintype "unspecified"))
      (node (ref "BUF12") (pin "10") (pinfunction "3G_10") (pintype "unspecified"))
      (node (ref "BUF12") (pin "13") (pinfunction "4G_13") (pintype "unspecified"))
      (node (ref "BUF12") (pin "4") (pinfunction "2G_4") (pintype "unspecified"))
      (node (ref "J10") (pin "5") (pinfunction "5_5") (pintype "unspecified"))
      (node (ref "NOR1") (pin "8") (pinfunction "2B_8") (pintype "unspecified"))
      (node (ref "ROM1") (pin "19") (pinfunction "DQ5_19") (pintype "unspecified"))
    )
    (net (code "68") (name "CW6") (class "Default")
      (node (ref "BUF13") (pin "1") (pinfunction "1G_1") (pintype "unspecified"))
      (node (ref "BUF13") (pin "10") (pinfunction "3G_10") (pintype "unspecified"))
      (node (ref "BUF13") (pin "13") (pinfunction "4G_13") (pintype "unspecified"))
      (node (ref "BUF13") (pin "4") (pinfunction "2G_4") (pintype "unspecified"))
      (node (ref "BUF14") (pin "1") (pinfunction "1G_1") (pintype "unspecified"))
      (node (ref "BUF14") (pin "10") (pinfunction "3G_10") (pintype "unspecified"))
      (node (ref "BUF14") (pin "13") (pinfunction "4G_13") (pintype "unspecified"))
      (node (ref "BUF14") (pin "4") (pinfunction "2G_4") (pintype "unspecified"))
      (node (ref "J10") (pin "4") (pinfunction "4_4") (pintype "unspecified"))
      (node (ref "NOR1") (pin "9") (pinfunction "2C_9") (pintype "unspecified"))
      (node (ref "ROM1") (pin "20") (pinfunction "DQ6_20") (pintype "unspecified"))
    )
    (net (code "69") (name "CW7") (class "Default")
      (node (ref "BUF15") (pin "1") (pinfunction "1G_1") (pintype "unspecified"))
      (node (ref "BUF15") (pin "10") (pinfunction "3G_10") (pintype "unspecified"))
      (node (ref "BUF15") (pin "13") (pinfunction "4G_13") (pintype "unspecified"))
      (node (ref "BUF15") (pin "4") (pinfunction "2G_4") (pintype "unspecified"))
      (node (ref "BUF16") (pin "1") (pinfunction "1G_1") (pintype "unspecified"))
      (node (ref "BUF16") (pin "10") (pinfunction "3G_10") (pintype "unspecified"))
      (node (ref "BUF16") (pin "13") (pinfunction "4G_13") (pintype "unspecified"))
      (node (ref "BUF16") (pin "4") (pinfunction "2G_4") (pintype "unspecified"))
      (node (ref "J10") (pin "3") (pinfunction "3_3") (pintype "unspecified"))
      (node (ref "NOR1") (pin "10") (pinfunction "2D_10") (pintype "unspecified"))
      (node (ref "ROM1") (pin "21") (pinfunction "DQ7_21") (pintype "unspecified"))
    )
    (net (code "70") (name "C_RP0") (class "Default")
      (node (ref "AND11") (pin "1") (pinfunction "1A_1") (pintype "unspecified"))
      (node (ref "AND11") (pin "9") (pinfunction "3A_9") (pintype "unspecified"))
      (node (ref "AND12") (pin "3") (pinfunction "2A_3") (pintype "unspecified"))
      (node (ref "AND6") (pin "6") (pinfunction "2Y_6") (pintype "unspecified"))
      (node (ref "INV3") (pin "1") (pinfunction "1A_1") (pintype "unspecified"))
    )
    (net (code "71") (name "C_RP0_INV") (class "Default")
      (node (ref "AND11") (pin "3") (pinfunction "2A_3") (pintype "unspecified"))
      (node (ref "AND12") (pin "1") (pinfunction "1A_1") (pintype "unspecified"))
      (node (ref "INV3") (pin "2") (pinfunction "1Y_2") (pintype "unspecified"))
    )
    (net (code "72") (name "C_RP1") (class "Default")
      (node (ref "AND11") (pin "10") (pinfunction "3B_10") (pintype "unspecified"))
      (node (ref "AND11") (pin "4") (pinfunction "2B_4") (pintype "unspecified"))
      (node (ref "AND12") (pin "4") (pinfunction "2B_4") (pintype "unspecified"))
      (node (ref "AND6") (pin "8") (pinfunction "3Y_8") (pintype "unspecified"))
      (node (ref "INV3") (pin "3") (pinfunction "2A_3") (pintype "unspecified"))
    )
    (net (code "73") (name "C_RP1_INV") (class "Default")
      (node (ref "AND11") (pin "2") (pinfunction "1B_2") (pintype "unspecified"))
      (node (ref "AND12") (pin "2") (pinfunction "1B_2") (pintype "unspecified"))
      (node (ref "INV3") (pin "4") (pinfunction "2Y_4") (pintype "unspecified"))
    )
    (net (code "74") (name "C_RP2") (class "Default")
      (node (ref "AND12") (pin "13") (pinfunction "1C_13") (pintype "unspecified"))
      (node (ref "AND12") (pin "5") (pinfunction "2C_5") (pintype "unspecified"))
      (node (ref "AND6") (pin "11") (pinfunction "4Y_11") (pintype "unspecified"))
      (node (ref "INV3") (pin "5") (pinfunction "3A_5") (pintype "unspecified"))
    )
    (net (code "75") (name "C_RP2_INV") (class "Default")
      (node (ref "AND11") (pin "11") (pinfunction "3C_11") (pintype "unspecified"))
      (node (ref "AND11") (pin "13") (pinfunction "1C_13") (pintype "unspecified"))
      (node (ref "AND11") (pin "5") (pinfunction "2C_5") (pintype "unspecified"))
      (node (ref "INV3") (pin "6") (pinfunction "3Y_6") (pintype "unspecified"))
    )
    (net (code "76") (name "GND") (class "Default")
      (node (ref "ADD1") (pin "7") (pinfunction "C0_7") (pintype "unspecified"))
      (node (ref "ADD1") (pin "8") (pinfunction "GND_8") (pintype "unspecified"))
      (node (ref "ADD2") (pin "8") (pinfunction "GND_8") (pintype "unspecified"))
      (node (ref "AND1") (pin "7") (pinfunction "GND_7") (pintype "unspecified"))
      (node (ref "AND11") (pin "7") (pinfunction "GND_7") (pintype "unspecified"))
      (node (ref "AND12") (pin "7") (pinfunction "GND_7") (pintype "unspecified"))
      (node (ref "AND2") (pin "7") (pinfunction "GND_7") (pintype "unspecified"))
      (node (ref "AND3") (pin "7") (pinfunction "GND_7") (pintype "unspecified"))
      (node (ref "AND4") (pin "7") (pinfunction "GND_7") (pintype "unspecified"))
      (node (ref "AND5") (pin "7") (pinfunction "GND_7") (pintype "unspecified"))
      (node (ref "AND6") (pin "7") (pinfunction "GND_7") (pintype "unspecified"))
      (node (ref "AND7") (pin "7") (pinfunction "GND_7") (pintype "unspecified"))
      (node (ref "AND8") (pin "7") (pinfunction "GND_7") (pintype "unspecified"))
      (node (ref "AND9") (pin "7") (pinfunction "GND_7") (pintype "unspecified"))
      (node (ref "BUF1") (pin "7") (pinfunction "GND_7") (pintype "unspecified"))
      (node (ref "BUF10") (pin "7") (pinfunction "GND_7") (pintype "unspecified"))
      (node (ref "BUF11") (pin "7") (pinfunction "GND_7") (pintype "unspecified"))
      (node (ref "BUF12") (pin "7") (pinfunction "GND_7") (pintype "unspecified"))
      (node (ref "BUF13") (pin "7") (pinfunction "GND_7") (pintype "unspecified"))
      (node (ref "BUF14") (pin "7") (pinfunction "GND_7") (pintype "unspecified"))
      (node (ref "BUF15") (pin "7") (pinfunction "GND_7") (pintype "unspecified"))
      (node (ref "BUF16") (pin "7") (pinfunction "GND_7") (pintype "unspecified"))
      (node (ref "BUF2") (pin "7") (pinfunction "GND_7") (pintype "unspecified"))
      (node (ref "BUF3") (pin "7") (pinfunction "GND_7") (pintype "unspecified"))
      (node (ref "BUF4") (pin "7") (pinfunction "GND_7") (pintype "unspecified"))
      (node (ref "BUF5") (pin "7") (pinfunction "GND_7") (pintype "unspecified"))
      (node (ref "BUF6") (pin "7") (pinfunction "GND_7") (pintype "unspecified"))
      (node (ref "BUF7") (pin "7") (pinfunction "GND_7") (pintype "unspecified"))
      (node (ref "BUF8") (pin "7") (pinfunction "GND_7") (pintype "unspecified"))
      (node (ref "BUF9") (pin "7") (pinfunction "GND_7") (pintype "unspecified"))
      (node (ref "C1") (pin "1") (pinfunction "1_1") (pintype "unspecified"))
      (node (ref "C10") (pin "1") (pinfunction "1_1") (pintype "unspecified"))
      (node (ref "C102") (pin "1") (pinfunction "1_1") (pintype "unspecified"))
      (node (ref "C103") (pin "1") (pinfunction "1_1") (pintype "unspecified"))
      (node (ref "C104") (pin "1") (pinfunction "1_1") (pintype "unspecified"))
      (node (ref "C105") (pin "1") (pinfunction "1_1") (pintype "unspecified"))
      (node (ref "C106") (pin "1") (pinfunction "1_1") (pintype "unspecified"))
      (node (ref "C107") (pin "1") (pinfunction "1_1") (pintype "unspecified"))
      (node (ref "C108") (pin "1") (pinfunction "1_1") (pintype "unspecified"))
      (node (ref "C109") (pin "1") (pinfunction "1_1") (pintype "unspecified"))
      (node (ref "C11") (pin "1") (pinfunction "1_1") (pintype "unspecified"))
      (node (ref "C110") (pin "1") (pinfunction "1_1") (pintype "unspecified"))
      (node (ref "C111") (pin "1") (pinfunction "1_1") (pintype "unspecified"))
      (node (ref "C112") (pin "1") (pinfunction "1_1") (pintype "unspecified"))
      (node (ref "C12") (pin "1") (pinfunction "1_1") (pintype "unspecified"))
      (node (ref "C13") (pin "1") (pinfunction "1_1") (pintype "unspecified"))
      (node (ref "C14") (pin "1") (pinfunction "1_1") (pintype "unspecified"))
      (node (ref "C15") (pin "2") (pinfunction "2_2") (pintype "input"))
      (node (ref "C2") (pin "2") (pinfunction "2_2") (pintype "unspecified"))
      (node (ref "C3") (pin "2") (pinfunction "2_2") (pintype "unspecified"))
      (node (ref "C4") (pin "1") (pinfunction "1_1") (pintype "unspecified"))
      (node (ref "C5") (pin "1") (pinfunction "1_1") (pintype "unspecified"))
      (node (ref "C58") (pin "1") (pinfunction "1_1") (pintype "unspecified"))
      (node (ref "C59") (pin "1") (pinfunction "1_1") (pintype "unspecified"))
      (node (ref "C6") (pin "1") (pinfunction "1_1") (pintype "unspecified"))
      (node (ref "C60") (pin "1") (pinfunction "1_1") (pintype "unspecified"))
      (node (ref "C61") (pin "1") (pinfunction "1_1") (pintype "unspecified"))
      (node (ref "C62") (pin "1") (pinfunction "1_1") (pintype "unspecified"))
      (node (ref "C63") (pin "1") (pinfunction "1_1") (pintype "unspecified"))
      (node (ref "C64") (pin "1") (pinfunction "1_1") (pintype "unspecified"))
      (node (ref "C7") (pin "1") (pinfunction "1_1") (pintype "unspecified"))
      (node (ref "C70") (pin "1") (pinfunction "1_1") (pintype "unspecified"))
      (node (ref "C71") (pin "1") (pinfunction "1_1") (pintype "unspecified"))
      (node (ref "C72") (pin "1") (pinfunction "1_1") (pintype "unspecified"))
      (node (ref "C73") (pin "1") (pinfunction "1_1") (pintype "unspecified"))
      (node (ref "C74") (pin "1") (pinfunction "1_1") (pintype "unspecified"))
      (node (ref "C75") (pin "1") (pinfunction "1_1") (pintype "unspecified"))
      (node (ref "C76") (pin "1") (pinfunction "1_1") (pintype "unspecified"))
      (node (ref "C77") (pin "1") (pinfunction "1_1") (pintype "unspecified"))
      (node (ref "C78") (pin "1") (pinfunction "1_1") (pintype "unspecified"))
      (node (ref "C79") (pin "1") (pinfunction "1_1") (pintype "unspecified"))
      (node (ref "C8") (pin "1") (pinfunction "1_1") (pintype "unspecified"))
      (node (ref "C85") (pin "1") (pinfunction "1_1") (pintype "unspecified"))
      (node (ref "C86") (pin "1") (pinfunction "1_1") (pintype "unspecified"))
      (node (ref "C87") (pin "1") (pinfunction "1_1") (pintype "unspecified"))
      (node (ref "C88") (pin "1") (pinfunction "1_1") (pintype "unspecified"))
      (node (ref "C89") (pin "1") (pinfunction "1_1") (pintype "unspecified"))
      (node (ref "C9") (pin "1") (pinfunction "1_1") (pintype "unspecified"))
      (node (ref "C90") (pin "1") (pinfunction "1_1") (pintype "unspecified"))
      (node (ref "C91") (pin "1") (pinfunction "1_1") (pintype "unspecified"))
      (node (ref "C92") (pin "1") (pinfunction "1_1") (pintype "unspecified"))
      (node (ref "C93") (pin "1") (pinfunction "1_1") (pintype "unspecified"))
      (node (ref "C94") (pin "1") (pinfunction "1_1") (pintype "unspecified"))
      (node (ref "C95") (pin "1") (pinfunction "1_1") (pintype "unspecified"))
      (node (ref "C96") (pin "1") (pinfunction "1_1") (pintype "unspecified"))
      (node (ref "INV1") (pin "7") (pinfunction "GND_7") (pintype "unspecified"))
      (node (ref "INV2") (pin "7") (pinfunction "GND_7") (pintype "unspecified"))
      (node (ref "INV3") (pin "7") (pinfunction "GND_7") (pintype "unspecified"))
      (node (ref "INV4") (pin "7") (pinfunction "GND_7") (pintype "unspecified"))
      (node (ref "J1") (pin "1") (pinfunction "1_1") (pintype "unspecified"))
      (node (ref "J10") (pin "1") (pinfunction "1_1") (pintype "unspecified"))
      (node (ref "J11") (pin "1") (pinfunction "1_1") (pintype "unspecified"))
      (node (ref "J12") (pin "1") (pinfunction "1_1") (pintype "unspecified"))
      (node (ref "J13") (pin "1") (pinfunction "1_1") (pintype "unspecified"))
      (node (ref "J16") (pin "1") (pinfunction "1_1") (pintype "unspecified"))
      (node (ref "J17") (pin "1") (pinfunction "1_1") (pintype "unspecified"))
      (node (ref "J18") (pin "1") (pinfunction "1_1") (pintype "unspecified"))
      (node (ref "J2") (pin "1") (pinfunction "1_1") (pintype "unspecified"))
      (node (ref "J3") (pin "2") (pinfunction "2_2") (pintype "unspecified"))
      (node (ref "J5") (pin "1") (pinfunction "1_1") (pintype "unspecified"))
      (node (ref "J6") (pin "1") (pinfunction "1_1") (pintype "unspecified"))
      (node (ref "J7") (pin "1") (pinfunction "1_1") (pintype "unspecified"))
      (node (ref "J8") (pin "1") (pinfunction "1_1") (pintype "input"))
      (node (ref "J9") (pin "1") (pinfunction "1_1") (pintype "unspecified"))
      (node (ref "NOR1") (pin "7") (pinfunction "GND_7") (pintype "unspecified"))
      (node (ref "NOR2") (pin "7") (pinfunction "GND_7") (pintype "unspecified"))
      (node (ref "NOR3") (pin "7") (pinfunction "GND_7") (pintype "unspecified"))
      (node (ref "R1") (pin "1") (pinfunction "1_1") (pintype "unspecified"))
      (node (ref "R10") (pin "1") (pinfunction "1_1") (pintype "unspecified"))
      (node (ref "R14") (pin "1") (pinfunction "1_1") (pintype "unspecified"))
      (node (ref "R15") (pin "1") (pinfunction "1_1") (pintype "unspecified"))
      (node (ref "R16") (pin "1") (pinfunction "1_1") (pintype "unspecified"))
      (node (ref "R17") (pin "1") (pinfunction "1_1") (pintype "unspecified"))
      (node (ref "R18") (pin "1") (pinfunction "1_1") (pintype "unspecified"))
      (node (ref "R19") (pin "1") (pinfunction "1_1") (pintype "unspecified"))
      (node (ref "R2") (pin "1") (pinfunction "1_1") (pintype "unspecified"))
      (node (ref "R20") (pin "1") (pinfunction "1_1") (pintype "unspecified"))
      (node (ref "R21") (pin "1") (pinfunction "1_1") (pintype "unspecified"))
      (node (ref "R3") (pin "1") (pinfunction "1_1") (pintype "unspecified"))
      (node (ref "R4") (pin "1") (pinfunction "1_1") (pintype "unspecified"))
      (node (ref "R5") (pin "1") (pinfunction "1_1") (pintype "unspecified"))
      (node (ref "R6") (pin "1") (pinfunction "1_1") (pintype "unspecified"))
      (node (ref "R7") (pin "1") (pinfunction "1_1") (pintype "unspecified"))
      (node (ref "R8") (pin "1") (pinfunction "1_1") (pintype "unspecified"))
      (node (ref "R9") (pin "1") (pinfunction "1_1") (pintype "unspecified"))
      (node (ref "RAM1") (pin "14") (pinfunction "Vss_14") (pintype "unspecified"))
      (node (ref "REG1") (pin "1") (pinfunction "OC#_1") (pintype "unspecified"))
      (node (ref "REG1") (pin "10") (pinfunction "GND_10") (pintype "unspecified"))
      (node (ref "REG2") (pin "1") (pinfunction "OC#_1") (pintype "unspecified"))
      (node (ref "REG2") (pin "10") (pinfunction "GND_10") (pintype "unspecified"))
      (node (ref "REG_A") (pin "1") (pinfunction "OC#_1") (pintype "unspecified"))
      (node (ref "REG_A") (pin "10") (pinfunction "GND_10") (pintype "unspecified"))
      (node (ref "REG_B") (pin "1") (pinfunction "OC#_1") (pintype "unspecified"))
      (node (ref "REG_B") (pin "10") (pinfunction "GND_10") (pintype "unspecified"))
      (node (ref "REG_IRO") (pin "1") (pinfunction "OC#_1") (pintype "unspecified"))
      (node (ref "REG_IRO") (pin "10") (pinfunction "GND_10") (pintype "unspecified"))
      (node (ref "REG_RP") (pin "1") (pinfunction "OC#_1") (pintype "unspecified"))
      (node (ref "REG_RP") (pin "10") (pinfunction "GND_10") (pintype "unspecified"))
      (node (ref "ROM1") (pin "16") (pinfunction "VSS_16") (pintype "unspecified"))
      (node (ref "ROM1") (pin "22") (pinfunction "CE#_22") (pintype "unspecified"))
      (node (ref "ROM1") (pin "24") (pinfunction "OE#_24") (pintype "unspecified"))
      (node (ref "ROM2") (pin "16") (pinfunction "VSS_16") (pintype "unspecified"))
      (node (ref "ROM2") (pin "22") (pinfunction "CE#_22") (pintype "unspecified"))
      (node (ref "ROM2") (pin "24") (pinfunction "OE#_24") (pintype "unspecified"))
      (node (ref "U1") (pin "1") (pinfunction "GND_1") (pintype "unspecified"))
      (node (ref "XOR1") (pin "7") (pinfunction "GND_7") (pintype "unspecified"))
      (node (ref "XOR2") (pin "7") (pinfunction "GND_7") (pintype "unspecified"))
      (node (ref "XOR3") (pin "7") (pinfunction "GND_7") (pintype "unspecified"))
      (node (ref "XOR4") (pin "7") (pinfunction "GND_7") (pintype "unspecified"))
      (node (ref "XOR5") (pin "7") (pinfunction "GND_7") (pintype "unspecified"))
      (node (ref "XOR6") (pin "7") (pinfunction "GND_7") (pintype "unspecified"))
    )
    (net (code "77") (name "IR0") (class "Default")
      (node (ref "AND1") (pin "1") (pinfunction "1A_1") (pintype "unspecified"))
      (node (ref "J12") (pin "10") (pinfunction "10_10") (pintype "unspecified"))
      (node (ref "REG1") (pin "2") (pinfunction "1Q_2") (pintype "unspecified"))
      (node (ref "ROM1") (pin "12") (pinfunction "A0_12") (pintype "unspecified"))
      (node (ref "ROM2") (pin "12") (pinfunction "A0_12") (pintype "unspecified"))
      (node (ref "XOR1") (pin "1") (pinfunction "1A_1") (pintype "unspecified"))
    )
    (net (code "78") (name "IR1") (class "Default")
      (node (ref "AND1") (pin "4") (pinfunction "2A_4") (pintype "unspecified"))
      (node (ref "J12") (pin "9") (pinfunction "9_9") (pintype "unspecified"))
      (node (ref "REG1") (pin "5") (pinfunction "2Q_5") (pintype "unspecified"))
      (node (ref "ROM1") (pin "11") (pinfunction "A1_11") (pintype "unspecified"))
      (node (ref "ROM2") (pin "11") (pinfunction "A1_11") (pintype "unspecified"))
      (node (ref "XOR1") (pin "4") (pinfunction "2A_4") (pintype "unspecified"))
    )
    (net (code "79") (name "IR2") (class "Default")
      (node (ref "AND1") (pin "9") (pinfunction "3A_9") (pintype "unspecified"))
      (node (ref "J12") (pin "8") (pinfunction "8_8") (pintype "unspecified"))
      (node (ref "REG1") (pin "6") (pinfunction "3Q_6") (pintype "unspecified"))
      (node (ref "ROM1") (pin "10") (pinfunction "A2_10") (pintype "unspecified"))
      (node (ref "ROM2") (pin "10") (pinfunction "A2_10") (pintype "unspecified"))
      (node (ref "XOR1") (pin "9") (pinfunction "3A_9") (pintype "unspecified"))
    )
    (net (code "80") (name "IR3") (class "Default")
      (node (ref "AND1") (pin "12") (pinfunction "4A_12") (pintype "unspecified"))
      (node (ref "J12") (pin "7") (pinfunction "7_7") (pintype "unspecified"))
      (node (ref "REG1") (pin "9") (pinfunction "4Q_9") (pintype "unspecified"))
      (node (ref "ROM1") (pin "9") (pinfunction "A3_9") (pintype "unspecified"))
      (node (ref "ROM2") (pin "9") (pinfunction "A3_9") (pintype "unspecified"))
      (node (ref "XOR1") (pin "12") (pinfunction "4A_12") (pintype "unspecified"))
    )
    (net (code "81") (name "IR4") (class "Default")
      (node (ref "AND2") (pin "1") (pinfunction "1A_1") (pintype "unspecified"))
      (node (ref "J12") (pin "6") (pinfunction "6_6") (pintype "unspecified"))
      (node (ref "REG1") (pin "12") (pinfunction "5Q_12") (pintype "unspecified"))
      (node (ref "ROM1") (pin "8") (pinfunction "A4_8") (pintype "unspecified"))
      (node (ref "ROM2") (pin "8") (pinfunction "A4_8") (pintype "unspecified"))
      (node (ref "XOR2") (pin "1") (pinfunction "1A_1") (pintype "unspecified"))
    )
    (net (code "82") (name "IR5") (class "Default")
      (node (ref "AND2") (pin "4") (pinfunction "2A_4") (pintype "unspecified"))
      (node (ref "J12") (pin "5") (pinfunction "5_5") (pintype "unspecified"))
      (node (ref "REG1") (pin "15") (pinfunction "6Q_15") (pintype "unspecified"))
      (node (ref "ROM1") (pin "7") (pinfunction "A5_7") (pintype "unspecified"))
      (node (ref "ROM2") (pin "7") (pinfunction "A5_7") (pintype "unspecified"))
      (node (ref "XOR2") (pin "4") (pinfunction "2A_4") (pintype "unspecified"))
    )
    (net (code "83") (name "IR6") (class "Default")
      (node (ref "AND2") (pin "9") (pinfunction "3A_9") (pintype "unspecified"))
      (node (ref "J12") (pin "4") (pinfunction "4_4") (pintype "unspecified"))
      (node (ref "REG1") (pin "16") (pinfunction "7Q_16") (pintype "unspecified"))
      (node (ref "ROM1") (pin "6") (pinfunction "A6_6") (pintype "unspecified"))
      (node (ref "ROM2") (pin "6") (pinfunction "A6_6") (pintype "unspecified"))
      (node (ref "XOR2") (pin "9") (pinfunction "3A_9") (pintype "unspecified"))
    )
    (net (code "84") (name "IR7") (class "Default")
      (node (ref "AND2") (pin "12") (pinfunction "4A_12") (pintype "unspecified"))
      (node (ref "J12") (pin "3") (pinfunction "3_3") (pintype "unspecified"))
      (node (ref "REG1") (pin "19") (pinfunction "8Q_19") (pintype "unspecified"))
      (node (ref "ROM1") (pin "5") (pinfunction "A7_5") (pintype "unspecified"))
      (node (ref "ROM2") (pin "5") (pinfunction "A7_5") (pintype "unspecified"))
      (node (ref "XOR2") (pin "12") (pinfunction "4A_12") (pintype "unspecified"))
    )
    (net (code "85") (name "IR8") (class "Default")
      (node (ref "AND3") (pin "1") (pinfunction "1A_1") (pintype "unspecified"))
      (node (ref "J13") (pin "10") (pinfunction "10_10") (pintype "unspecified"))
      (node (ref "REG2") (pin "2") (pinfunction "1Q_2") (pintype "unspecified"))
      (node (ref "ROM1") (pin "27") (pinfunction "A8_27") (pintype "unspecified"))
      (node (ref "ROM2") (pin "27") (pinfunction "A8_27") (pintype "unspecified"))
      (node (ref "XOR3") (pin "1") (pinfunction "1A_1") (pintype "unspecified"))
    )
    (net (code "86") (name "IR9") (class "Default")
      (node (ref "AND3") (pin "4") (pinfunction "2A_4") (pintype "unspecified"))
      (node (ref "J13") (pin "9") (pinfunction "9_9") (pintype "unspecified"))
      (node (ref "REG2") (pin "5") (pinfunction "2Q_5") (pintype "unspecified"))
      (node (ref "ROM1") (pin "26") (pinfunction "A9_26") (pintype "unspecified"))
      (node (ref "ROM2") (pin "26") (pinfunction "A9_26") (pintype "unspecified"))
      (node (ref "XOR3") (pin "4") (pinfunction "2A_4") (pintype "unspecified"))
    )
    (net (code "87") (name "IR10") (class "Default")
      (node (ref "AND3") (pin "9") (pinfunction "3A_9") (pintype "unspecified"))
      (node (ref "J13") (pin "8") (pinfunction "8_8") (pintype "unspecified"))
      (node (ref "REG2") (pin "6") (pinfunction "3Q_6") (pintype "unspecified"))
      (node (ref "ROM1") (pin "23") (pinfunction "A10_23") (pintype "unspecified"))
      (node (ref "ROM2") (pin "23") (pinfunction "A10_23") (pintype "unspecified"))
      (node (ref "XOR3") (pin "9") (pinfunction "3A_9") (pintype "unspecified"))
    )
    (net (code "88") (name "IR11") (class "Default")
      (node (ref "AND3") (pin "12") (pinfunction "4A_12") (pintype "unspecified"))
      (node (ref "J13") (pin "7") (pinfunction "7_7") (pintype "unspecified"))
      (node (ref "REG2") (pin "9") (pinfunction "4Q_9") (pintype "unspecified"))
      (node (ref "ROM1") (pin "25") (pinfunction "A11_25") (pintype "unspecified"))
      (node (ref "ROM2") (pin "25") (pinfunction "A11_25") (pintype "unspecified"))
      (node (ref "XOR3") (pin "12") (pinfunction "4A_12") (pintype "unspecified"))
    )
    (net (code "89") (name "IR12") (class "Default")
      (node (ref "AND4") (pin "1") (pinfunction "1A_1") (pintype "unspecified"))
      (node (ref "J13") (pin "6") (pinfunction "6_6") (pintype "unspecified"))
      (node (ref "REG2") (pin "12") (pinfunction "5Q_12") (pintype "unspecified"))
      (node (ref "ROM1") (pin "4") (pinfunction "A12_4") (pintype "unspecified"))
      (node (ref "ROM2") (pin "4") (pinfunction "A12_4") (pintype "unspecified"))
      (node (ref "XOR4") (pin "1") (pinfunction "1A_1") (pintype "unspecified"))
    )
    (net (code "90") (name "IR13") (class "Default")
      (node (ref "AND4") (pin "4") (pinfunction "2A_4") (pintype "unspecified"))
      (node (ref "J13") (pin "5") (pinfunction "5_5") (pintype "unspecified"))
      (node (ref "REG2") (pin "15") (pinfunction "6Q_15") (pintype "unspecified"))
      (node (ref "ROM1") (pin "28") (pinfunction "A13_28") (pintype "unspecified"))
      (node (ref "ROM2") (pin "28") (pinfunction "A13_28") (pintype "unspecified"))
      (node (ref "XOR4") (pin "4") (pinfunction "2A_4") (pintype "unspecified"))
    )
    (net (code "91") (name "IR14") (class "Default")
      (node (ref "AND4") (pin "9") (pinfunction "3A_9") (pintype "unspecified"))
      (node (ref "J13") (pin "4") (pinfunction "4_4") (pintype "unspecified"))
      (node (ref "REG2") (pin "16") (pinfunction "7Q_16") (pintype "unspecified"))
      (node (ref "ROM1") (pin "29") (pinfunction "A14_29") (pintype "unspecified"))
      (node (ref "ROM2") (pin "29") (pinfunction "A14_29") (pintype "unspecified"))
      (node (ref "XOR4") (pin "9") (pinfunction "3A_9") (pintype "unspecified"))
    )
    (net (code "92") (name "IR15") (class "Default")
      (node (ref "AND4") (pin "12") (pinfunction "4A_12") (pintype "unspecified"))
      (node (ref "J13") (pin "3") (pinfunction "3_3") (pintype "unspecified"))
      (node (ref "REG2") (pin "19") (pinfunction "8Q_19") (pintype "unspecified"))
      (node (ref "ROM1") (pin "3") (pinfunction "A15_3") (pintype "unspecified"))
      (node (ref "ROM2") (pin "3") (pinfunction "A15_3") (pintype "unspecified"))
      (node (ref "XOR4") (pin "12") (pinfunction "4A_12") (pintype "unspecified"))
    )
    (net (code "93") (name "IRC0") (class "Default")
      (node (ref "AND1") (pin "3") (pinfunction "1Y_3") (pintype "unspecified"))
      (node (ref "AND1") (pin "5") (pinfunction "2B_5") (pintype "unspecified"))
      (node (ref "XOR1") (pin "5") (pinfunction "2B_5") (pintype "unspecified"))
    )
    (net (code "94") (name "IRC1") (class "Default")
      (node (ref "AND1") (pin "10") (pinfunction "3B_10") (pintype "unspecified"))
      (node (ref "AND1") (pin "6") (pinfunction "2Y_6") (pintype "unspecified"))
      (node (ref "XOR1") (pin "10") (pinfunction "3B_10") (pintype "unspecified"))
    )
    (net (code "95") (name "IRC2") (class "Default")
      (node (ref "AND1") (pin "13") (pinfunction "4B_13") (pintype "unspecified"))
      (node (ref "AND1") (pin "8") (pinfunction "3Y_8") (pintype "unspecified"))
      (node (ref "XOR1") (pin "13") (pinfunction "4B_13") (pintype "unspecified"))
    )
    (net (code "96") (name "IRC3") (class "Default")
      (node (ref "AND1") (pin "11") (pinfunction "4Y_11") (pintype "unspecified"))
      (node (ref "AND2") (pin "2") (pinfunction "1B_2") (pintype "unspecified"))
      (node (ref "XOR2") (pin "2") (pinfunction "1B_2") (pintype "unspecified"))
    )
    (net (code "97") (name "IRC4") (class "Default")
      (node (ref "AND2") (pin "3") (pinfunction "1Y_3") (pintype "unspecified"))
      (node (ref "AND2") (pin "5") (pinfunction "2B_5") (pintype "unspecified"))
      (node (ref "XOR2") (pin "5") (pinfunction "2B_5") (pintype "unspecified"))
    )
    (net (code "98") (name "IRC5") (class "Default")
      (node (ref "AND2") (pin "10") (pinfunction "3B_10") (pintype "unspecified"))
      (node (ref "AND2") (pin "6") (pinfunction "2Y_6") (pintype "unspecified"))
      (node (ref "XOR2") (pin "10") (pinfunction "3B_10") (pintype "unspecified"))
    )
    (net (code "99") (name "IRC6") (class "Default")
      (node (ref "AND2") (pin "13") (pinfunction "4B_13") (pintype "unspecified"))
      (node (ref "AND2") (pin "8") (pinfunction "3Y_8") (pintype "unspecified"))
      (node (ref "XOR2") (pin "13") (pinfunction "4B_13") (pintype "unspecified"))
    )
    (net (code "100") (name "IRC7") (class "Default")
      (node (ref "AND2") (pin "11") (pinfunction "4Y_11") (pintype "unspecified"))
      (node (ref "AND3") (pin "2") (pinfunction "1B_2") (pintype "unspecified"))
      (node (ref "XOR3") (pin "2") (pinfunction "1B_2") (pintype "unspecified"))
    )
    (net (code "101") (name "IRC8") (class "Default")
      (node (ref "AND3") (pin "3") (pinfunction "1Y_3") (pintype "unspecified"))
      (node (ref "AND3") (pin "5") (pinfunction "2B_5") (pintype "unspecified"))
      (node (ref "XOR3") (pin "5") (pinfunction "2B_5") (pintype "unspecified"))
    )
    (net (code "102") (name "IRC9") (class "Default")
      (node (ref "AND3") (pin "10") (pinfunction "3B_10") (pintype "unspecified"))
      (node (ref "AND3") (pin "6") (pinfunction "2Y_6") (pintype "unspecified"))
      (node (ref "XOR3") (pin "10") (pinfunction "3B_10") (pintype "unspecified"))
    )
    (net (code "103") (name "IRC10") (class "Default")
      (node (ref "AND3") (pin "13") (pinfunction "4B_13") (pintype "unspecified"))
      (node (ref "AND3") (pin "8") (pinfunction "3Y_8") (pintype "unspecified"))
      (node (ref "XOR3") (pin "13") (pinfunction "4B_13") (pintype "unspecified"))
    )
    (net (code "104") (name "IRC11") (class "Default")
      (node (ref "AND3") (pin "11") (pinfunction "4Y_11") (pintype "unspecified"))
      (node (ref "AND4") (pin "2") (pinfunction "1B_2") (pintype "unspecified"))
      (node (ref "XOR4") (pin "2") (pinfunction "1B_2") (pintype "unspecified"))
    )
    (net (code "105") (name "IRC12") (class "Default")
      (node (ref "AND4") (pin "3") (pinfunction "1Y_3") (pintype "unspecified"))
      (node (ref "AND4") (pin "5") (pinfunction "2B_5") (pintype "unspecified"))
      (node (ref "XOR4") (pin "5") (pinfunction "2B_5") (pintype "unspecified"))
    )
    (net (code "106") (name "IRC13") (class "Default")
      (node (ref "AND4") (pin "10") (pinfunction "3B_10") (pintype "unspecified"))
      (node (ref "AND4") (pin "6") (pinfunction "2Y_6") (pintype "unspecified"))
      (node (ref "XOR4") (pin "10") (pinfunction "3B_10") (pintype "unspecified"))
    )
    (net (code "107") (name "IRC14") (class "Default")
      (node (ref "AND4") (pin "13") (pinfunction "4B_13") (pintype "unspecified"))
      (node (ref "AND4") (pin "8") (pinfunction "3Y_8") (pintype "unspecified"))
      (node (ref "XOR4") (pin "13") (pinfunction "4B_13") (pintype "unspecified"))
    )
    (net (code "108") (name "IRC15") (class "Default")
      (node (ref "AND4") (pin "11") (pinfunction "4Y_11") (pintype "unspecified"))
      (node (ref "J15") (pin "3") (pinfunction "3_3") (pintype "input"))
    )
    (net (code "109") (name "IRI0") (class "Default")
      (node (ref "BUF1") (pin "2") (pinfunction "1A_2") (pintype "unspecified"))
      (node (ref "XOR1") (pin "3") (pinfunction "1Y_3") (pintype "unspecified"))
    )
    (net (code "110") (name "IRI1") (class "Default")
      (node (ref "BUF1") (pin "5") (pinfunction "2A_5") (pintype "unspecified"))
      (node (ref "XOR1") (pin "6") (pinfunction "2Y_6") (pintype "unspecified"))
    )
    (net (code "111") (name "IRI2") (class "Default")
      (node (ref "BUF1") (pin "9") (pinfunction "3A_9") (pintype "unspecified"))
      (node (ref "XOR1") (pin "8") (pinfunction "3Y_8") (pintype "unspecified"))
    )
    (net (code "112") (name "IRI3") (class "Default")
      (node (ref "BUF1") (pin "12") (pinfunction "4A_12") (pintype "unspecified"))
      (node (ref "XOR1") (pin "11") (pinfunction "4Y_11") (pintype "unspecified"))
    )
    (net (code "113") (name "IRI4") (class "Default")
      (node (ref "BUF2") (pin "2") (pinfunction "1A_2") (pintype "unspecified"))
      (node (ref "XOR2") (pin "3") (pinfunction "1Y_3") (pintype "unspecified"))
    )
    (net (code "114") (name "IRI5") (class "Default")
      (node (ref "BUF2") (pin "5") (pinfunction "2A_5") (pintype "unspecified"))
      (node (ref "XOR2") (pin "6") (pinfunction "2Y_6") (pintype "unspecified"))
    )
    (net (code "115") (name "IRI6") (class "Default")
      (node (ref "BUF2") (pin "9") (pinfunction "3A_9") (pintype "unspecified"))
      (node (ref "XOR2") (pin "8") (pinfunction "3Y_8") (pintype "unspecified"))
    )
    (net (code "116") (name "IRI7") (class "Default")
      (node (ref "BUF2") (pin "12") (pinfunction "4A_12") (pintype "unspecified"))
      (node (ref "XOR2") (pin "11") (pinfunction "4Y_11") (pintype "unspecified"))
    )
    (net (code "117") (name "IRI8") (class "Default")
      (node (ref "BUF3") (pin "2") (pinfunction "1A_2") (pintype "unspecified"))
      (node (ref "XOR3") (pin "3") (pinfunction "1Y_3") (pintype "unspecified"))
    )
    (net (code "118") (name "IRI9") (class "Default")
      (node (ref "BUF3") (pin "5") (pinfunction "2A_5") (pintype "unspecified"))
      (node (ref "XOR3") (pin "6") (pinfunction "2Y_6") (pintype "unspecified"))
    )
    (net (code "119") (name "IRI10") (class "Default")
      (node (ref "BUF3") (pin "9") (pinfunction "3A_9") (pintype "unspecified"))
      (node (ref "XOR3") (pin "8") (pinfunction "3Y_8") (pintype "unspecified"))
    )
    (net (code "120") (name "IRI11") (class "Default")
      (node (ref "BUF3") (pin "12") (pinfunction "4A_12") (pintype "unspecified"))
      (node (ref "XOR3") (pin "11") (pinfunction "4Y_11") (pintype "unspecified"))
    )
    (net (code "121") (name "IRI12") (class "Default")
      (node (ref "BUF4") (pin "2") (pinfunction "1A_2") (pintype "unspecified"))
      (node (ref "XOR4") (pin "3") (pinfunction "1Y_3") (pintype "unspecified"))
    )
    (net (code "122") (name "IRI13") (class "Default")
      (node (ref "BUF4") (pin "5") (pinfunction "2A_5") (pintype "unspecified"))
      (node (ref "XOR4") (pin "6") (pinfunction "2Y_6") (pintype "unspecified"))
    )
    (net (code "123") (name "IRI14") (class "Default")
      (node (ref "BUF4") (pin "9") (pinfunction "3A_9") (pintype "unspecified"))
      (node (ref "XOR4") (pin "8") (pinfunction "3Y_8") (pintype "unspecified"))
    )
    (net (code "124") (name "IRI15") (class "Default")
      (node (ref "BUF4") (pin "12") (pinfunction "4A_12") (pintype "unspecified"))
      (node (ref "XOR4") (pin "11") (pinfunction "4Y_11") (pintype "unspecified"))
    )
    (net (code "125") (name "IR_IN0") (class "Default")
      (node (ref "BUF1") (pin "3") (pinfunction "1Y_3") (pintype "unspecified"))
      (node (ref "BUF5") (pin "3") (pinfunction "1Y_3") (pintype "unspecified"))
      (node (ref "R2") (pin "2") (pinfunction "2_2") (pintype "unspecified"))
      (node (ref "REG1") (pin "3") (pinfunction "1D_3") (pintype "unspecified"))
    )
    (net (code "126") (name "IR_IN1") (class "Default")
      (node (ref "BUF1") (pin "6") (pinfunction "2Y_6") (pintype "unspecified"))
      (node (ref "BUF5") (pin "6") (pinfunction "2Y_6") (pintype "unspecified"))
      (node (ref "R3") (pin "2") (pinfunction "2_2") (pintype "unspecified"))
      (node (ref "REG1") (pin "4") (pinfunction "2D_4") (pintype "unspecified"))
    )
    (net (code "127") (name "IR_IN2") (class "Default")
      (node (ref "BUF1") (pin "8") (pinfunction "3Y_8") (pintype "unspecified"))
      (node (ref "BUF5") (pin "8") (pinfunction "3Y_8") (pintype "unspecified"))
      (node (ref "R4") (pin "2") (pinfunction "2_2") (pintype "unspecified"))
      (node (ref "REG1") (pin "7") (pinfunction "3D_7") (pintype "unspecified"))
    )
    (net (code "128") (name "IR_IN3") (class "Default")
      (node (ref "BUF1") (pin "11") (pinfunction "4Y_11") (pintype "unspecified"))
      (node (ref "BUF5") (pin "11") (pinfunction "4Y_11") (pintype "unspecified"))
      (node (ref "R5") (pin "2") (pinfunction "2_2") (pintype "unspecified"))
      (node (ref "REG1") (pin "8") (pinfunction "4D_8") (pintype "unspecified"))
    )
    (net (code "129") (name "IR_IN4") (class "Default")
      (node (ref "BUF2") (pin "3") (pinfunction "1Y_3") (pintype "unspecified"))
      (node (ref "BUF6") (pin "3") (pinfunction "1Y_3") (pintype "unspecified"))
      (node (ref "R6") (pin "2") (pinfunction "2_2") (pintype "unspecified"))
      (node (ref "REG1") (pin "13") (pinfunction "5D_13") (pintype "unspecified"))
    )
    (net (code "130") (name "IR_IN5") (class "Default")
      (node (ref "BUF2") (pin "6") (pinfunction "2Y_6") (pintype "unspecified"))
      (node (ref "BUF6") (pin "6") (pinfunction "2Y_6") (pintype "unspecified"))
      (node (ref "R7") (pin "2") (pinfunction "2_2") (pintype "unspecified"))
      (node (ref "REG1") (pin "14") (pinfunction "6D_14") (pintype "unspecified"))
    )
    (net (code "131") (name "IR_IN6") (class "Default")
      (node (ref "BUF2") (pin "8") (pinfunction "3Y_8") (pintype "unspecified"))
      (node (ref "BUF6") (pin "8") (pinfunction "3Y_8") (pintype "unspecified"))
      (node (ref "R8") (pin "2") (pinfunction "2_2") (pintype "unspecified"))
      (node (ref "REG1") (pin "17") (pinfunction "7D_17") (pintype "unspecified"))
    )
    (net (code "132") (name "IR_IN7") (class "Default")
      (node (ref "BUF2") (pin "11") (pinfunction "4Y_11") (pintype "unspecified"))
      (node (ref "BUF6") (pin "11") (pinfunction "4Y_11") (pintype "unspecified"))
      (node (ref "R9") (pin "2") (pinfunction "2_2") (pintype "unspecified"))
      (node (ref "REG1") (pin "18") (pinfunction "8D_18") (pintype "unspecified"))
    )
    (net (code "133") (name "IR_IN8") (class "Default")
      (node (ref "BUF3") (pin "3") (pinfunction "1Y_3") (pintype "unspecified"))
      (node (ref "BUF7") (pin "3") (pinfunction "1Y_3") (pintype "unspecified"))
      (node (ref "REG2") (pin "3") (pinfunction "1D_3") (pintype "unspecified"))
    )
    (net (code "134") (name "IR_IN9") (class "Default")
      (node (ref "BUF3") (pin "6") (pinfunction "2Y_6") (pintype "unspecified"))
      (node (ref "BUF7") (pin "6") (pinfunction "2Y_6") (pintype "unspecified"))
      (node (ref "REG2") (pin "4") (pinfunction "2D_4") (pintype "unspecified"))
    )
    (net (code "135") (name "IR_IN10") (class "Default")
      (node (ref "BUF3") (pin "8") (pinfunction "3Y_8") (pintype "unspecified"))
      (node (ref "BUF7") (pin "8") (pinfunction "3Y_8") (pintype "unspecified"))
      (node (ref "REG2") (pin "7") (pinfunction "3D_7") (pintype "unspecified"))
    )
    (net (code "136") (name "IR_IN11") (class "Default")
      (node (ref "BUF3") (pin "11") (pinfunction "4Y_11") (pintype "unspecified"))
      (node (ref "BUF7") (pin "11") (pinfunction "4Y_11") (pintype "unspecified"))
      (node (ref "REG2") (pin "8") (pinfunction "4D_8") (pintype "unspecified"))
    )
    (net (code "137") (name "IR_IN12") (class "Default")
      (node (ref "BUF4") (pin "3") (pinfunction "1Y_3") (pintype "unspecified"))
      (node (ref "BUF8") (pin "3") (pinfunction "1Y_3") (pintype "unspecified"))
      (node (ref "REG2") (pin "13") (pinfunction "5D_13") (pintype "unspecified"))
    )
    (net (code "138") (name "IR_IN13") (class "Default")
      (node (ref "BUF4") (pin "6") (pinfunction "2Y_6") (pintype "unspecified"))
      (node (ref "BUF8") (pin "6") (pinfunction "2Y_6") (pintype "unspecified"))
      (node (ref "REG2") (pin "14") (pinfunction "6D_14") (pintype "unspecified"))
    )
    (net (code "139") (name "IR_IN14") (class "Default")
      (node (ref "BUF4") (pin "8") (pinfunction "3Y_8") (pintype "unspecified"))
      (node (ref "BUF8") (pin "8") (pinfunction "3Y_8") (pintype "unspecified"))
      (node (ref "REG2") (pin "17") (pinfunction "7D_17") (pintype "unspecified"))
    )
    (net (code "140") (name "IR_IN15") (class "Default")
      (node (ref "BUF4") (pin "11") (pinfunction "4Y_11") (pintype "unspecified"))
      (node (ref "BUF8") (pin "11") (pinfunction "4Y_11") (pintype "unspecified"))
      (node (ref "REG2") (pin "18") (pinfunction "8D_18") (pintype "unspecified"))
    )
    (net (code "141") (name "IR_O8") (class "Default")
      (node (ref "BUF7") (pin "2") (pinfunction "1A_2") (pintype "unspecified"))
      (node (ref "REG_IRO") (pin "2") (pinfunction "1Q_2") (pintype "unspecified"))
    )
    (net (code "142") (name "IR_O9") (class "Default")
      (node (ref "BUF7") (pin "5") (pinfunction "2A_5") (pintype "unspecified"))
      (node (ref "REG_IRO") (pin "5") (pinfunction "2Q_5") (pintype "unspecified"))
    )
    (net (code "143") (name "IR_O10") (class "Default")
      (node (ref "BUF7") (pin "9") (pinfunction "3A_9") (pintype "unspecified"))
      (node (ref "REG_IRO") (pin "6") (pinfunction "3Q_6") (pintype "unspecified"))
    )
    (net (code "144") (name "IR_O11") (class "Default")
      (node (ref "BUF7") (pin "12") (pinfunction "4A_12") (pintype "unspecified"))
      (node (ref "REG_IRO") (pin "9") (pinfunction "4Q_9") (pintype "unspecified"))
    )
    (net (code "145") (name "IR_O12") (class "Default")
      (node (ref "BUF8") (pin "2") (pinfunction "1A_2") (pintype "unspecified"))
      (node (ref "REG_IRO") (pin "12") (pinfunction "5Q_12") (pintype "unspecified"))
    )
    (net (code "146") (name "IR_O13") (class "Default")
      (node (ref "BUF8") (pin "5") (pinfunction "2A_5") (pintype "unspecified"))
      (node (ref "REG_IRO") (pin "15") (pinfunction "6Q_15") (pintype "unspecified"))
    )
    (net (code "147") (name "IR_O14") (class "Default")
      (node (ref "BUF8") (pin "9") (pinfunction "3A_9") (pintype "unspecified"))
      (node (ref "REG_IRO") (pin "16") (pinfunction "7Q_16") (pintype "unspecified"))
    )
    (net (code "148") (name "IR_O15") (class "Default")
      (node (ref "BUF8") (pin "12") (pinfunction "4A_12") (pintype "unspecified"))
      (node (ref "REG_IRO") (pin "19") (pinfunction "8Q_19") (pintype "unspecified"))
    )
    (net (code "149") (name "IR_OE") (class "Default")
      (node (ref "BUF5") (pin "1") (pinfunction "1G_1") (pintype "unspecified"))
      (node (ref "BUF5") (pin "10") (pinfunction "3G_10") (pintype "unspecified"))
      (node (ref "BUF5") (pin "13") (pinfunction "4G_13") (pintype "unspecified"))
      (node (ref "BUF5") (pin "4") (pinfunction "2G_4") (pintype "unspecified"))
      (node (ref "BUF6") (pin "1") (pinfunction "1G_1") (pintype "unspecified"))
      (node (ref "BUF6") (pin "10") (pinfunction "3G_10") (pintype "unspecified"))
      (node (ref "BUF6") (pin "13") (pinfunction "4G_13") (pintype "unspecified"))
      (node (ref "BUF6") (pin "4") (pinfunction "2G_4") (pintype "unspecified"))
      (node (ref "BUF7") (pin "1") (pinfunction "1G_1") (pintype "unspecified"))
      (node (ref "BUF7") (pin "10") (pinfunction "3G_10") (pintype "unspecified"))
      (node (ref "BUF7") (pin "13") (pinfunction "4G_13") (pintype "unspecified"))
      (node (ref "BUF7") (pin "4") (pinfunction "2G_4") (pintype "unspecified"))
      (node (ref "BUF8") (pin "1") (pinfunction "1G_1") (pintype "unspecified"))
      (node (ref "BUF8") (pin "10") (pinfunction "3G_10") (pintype "unspecified"))
      (node (ref "BUF8") (pin "13") (pinfunction "4G_13") (pintype "unspecified"))
      (node (ref "BUF8") (pin "4") (pinfunction "2G_4") (pintype "unspecified"))
      (node (ref "NOR2") (pin "4") (pinfunction "2A_4") (pintype "unspecified"))
      (node (ref "NOR3") (pin "6") (pinfunction "2Y_6") (pintype "unspecified"))
    )
    (net (code "150") (name "IR_OE_INV") (class "Default")
      (node (ref "BUF1") (pin "1") (pinfunction "1G_1") (pintype "unspecified"))
      (node (ref "BUF1") (pin "10") (pinfunction "3G_10") (pintype "unspecified"))
      (node (ref "BUF1") (pin "13") (pinfunction "4G_13") (pintype "unspecified"))
      (node (ref "BUF1") (pin "4") (pinfunction "2G_4") (pintype "unspecified"))
      (node (ref "BUF2") (pin "1") (pinfunction "1G_1") (pintype "unspecified"))
      (node (ref "BUF2") (pin "10") (pinfunction "3G_10") (pintype "unspecified"))
      (node (ref "BUF2") (pin "13") (pinfunction "4G_13") (pintype "unspecified"))
      (node (ref "BUF2") (pin "4") (pinfunction "2G_4") (pintype "unspecified"))
      (node (ref "BUF3") (pin "1") (pinfunction "1G_1") (pintype "unspecified"))
      (node (ref "BUF3") (pin "10") (pinfunction "3G_10") (pintype "unspecified"))
      (node (ref "BUF3") (pin "13") (pinfunction "4G_13") (pintype "unspecified"))
      (node (ref "BUF3") (pin "4") (pinfunction "2G_4") (pintype "unspecified"))
      (node (ref "BUF4") (pin "1") (pinfunction "1G_1") (pintype "unspecified"))
      (node (ref "BUF4") (pin "10") (pinfunction "3G_10") (pintype "unspecified"))
      (node (ref "BUF4") (pin "13") (pinfunction "4G_13") (pintype "unspecified"))
      (node (ref "BUF4") (pin "4") (pinfunction "2G_4") (pintype "unspecified"))
      (node (ref "NOR2") (pin "6") (pinfunction "2Y_6") (pintype "unspecified"))
    )
    (net (code "151") (name "LIT0") (class "Default")
      (node (ref "BUF9") (pin "2") (pinfunction "1A_2") (pintype "unspecified"))
      (node (ref "J11") (pin "10") (pinfunction "10_10") (pintype "unspecified"))
      (node (ref "ROM2") (pin "13") (pinfunction "DQ0_13") (pintype "unspecified"))
    )
    (net (code "152") (name "LIT1") (class "Default")
      (node (ref "BUF9") (pin "5") (pinfunction "2A_5") (pintype "unspecified"))
      (node (ref "J11") (pin "9") (pinfunction "9_9") (pintype "unspecified"))
      (node (ref "ROM2") (pin "14") (pinfunction "DQ1_14") (pintype "unspecified"))
    )
    (net (code "153") (name "LIT2") (class "Default")
      (node (ref "BUF9") (pin "9") (pinfunction "3A_9") (pintype "unspecified"))
      (node (ref "J11") (pin "8") (pinfunction "8_8") (pintype "unspecified"))
      (node (ref "ROM2") (pin "15") (pinfunction "DQ2_15") (pintype "unspecified"))
    )
    (net (code "154") (name "LIT3") (class "Default")
      (node (ref "BUF9") (pin "12") (pinfunction "4A_12") (pintype "unspecified"))
      (node (ref "J11") (pin "7") (pinfunction "7_7") (pintype "unspecified"))
      (node (ref "ROM2") (pin "17") (pinfunction "DQ3_17") (pintype "unspecified"))
    )
    (net (code "155") (name "LIT4") (class "Default")
      (node (ref "BUF10") (pin "2") (pinfunction "1A_2") (pintype "unspecified"))
      (node (ref "J11") (pin "6") (pinfunction "6_6") (pintype "unspecified"))
      (node (ref "ROM2") (pin "18") (pinfunction "DQ4_18") (pintype "unspecified"))
    )
    (net (code "156") (name "LIT5") (class "Default")
      (node (ref "BUF10") (pin "5") (pinfunction "2A_5") (pintype "unspecified"))
      (node (ref "J11") (pin "5") (pinfunction "5_5") (pintype "unspecified"))
      (node (ref "ROM2") (pin "19") (pinfunction "DQ5_19") (pintype "unspecified"))
    )
    (net (code "157") (name "LIT6") (class "Default")
      (node (ref "BUF10") (pin "9") (pinfunction "3A_9") (pintype "unspecified"))
      (node (ref "J11") (pin "4") (pinfunction "4_4") (pintype "unspecified"))
      (node (ref "ROM2") (pin "20") (pinfunction "DQ6_20") (pintype "unspecified"))
    )
    (net (code "158") (name "LIT7") (class "Default")
      (node (ref "BUF10") (pin "12") (pinfunction "4A_12") (pintype "unspecified"))
      (node (ref "J11") (pin "3") (pinfunction "3_3") (pintype "unspecified"))
      (node (ref "ROM2") (pin "21") (pinfunction "DQ7_21") (pintype "unspecified"))
    )
    (net (code "159") (name "LIT_EN") (class "Default")
      (node (ref "BUF10") (pin "1") (pinfunction "1G_1") (pintype "unspecified"))
      (node (ref "BUF10") (pin "10") (pinfunction "3G_10") (pintype "unspecified"))
      (node (ref "BUF10") (pin "13") (pinfunction "4G_13") (pintype "unspecified"))
      (node (ref "BUF10") (pin "4") (pinfunction "2G_4") (pintype "unspecified"))
      (node (ref "BUF9") (pin "1") (pinfunction "1G_1") (pintype "unspecified"))
      (node (ref "BUF9") (pin "10") (pinfunction "3G_10") (pintype "unspecified"))
      (node (ref "BUF9") (pin "13") (pinfunction "4G_13") (pintype "unspecified"))
      (node (ref "BUF9") (pin "4") (pinfunction "2G_4") (pintype "unspecified"))
      (node (ref "NOR1") (pin "6") (pinfunction "2Y_6") (pintype "unspecified"))
    )
    (net (code "160") (name "Net-(ADD1-C4)") (class "Default")
      (node (ref "ADD1") (pin "9") (pinfunction "C4_9") (pintype "unspecified"))
      (node (ref "ADD2") (pin "7") (pinfunction "C0_7") (pintype "unspecified"))
    )
    (net (code "161") (name "Net-(AND5-1Y)") (class "Default")
      (node (ref "AND5") (pin "3") (pinfunction "1Y_3") (pintype "unspecified"))
      (node (ref "INV3") (pin "13") (pinfunction "6A_13") (pintype "unspecified"))
    )
    (net (code "162") (name "Net-(AND5-2Y)") (class "Default")
      (node (ref "AND5") (pin "6") (pinfunction "2Y_6") (pintype "unspecified"))
      (node (ref "INV3") (pin "11") (pinfunction "5A_11") (pintype "unspecified"))
    )
    (net (code "163") (name "Net-(AND6-2B)") (class "Default")
      (node (ref "AND6") (pin "10") (pinfunction "3B_10") (pintype "unspecified"))
      (node (ref "AND6") (pin "13") (pinfunction "4B_13") (pintype "unspecified"))
      (node (ref "AND6") (pin "5") (pinfunction "2B_5") (pintype "unspecified"))
      (node (ref "NOR1") (pin "5") (pinfunction "1Y_5") (pintype "unspecified"))
    )
    (net (code "164") (name "Net-(AND9-1A)") (class "Default")
      (node (ref "AND9") (pin "1") (pinfunction "1A_1") (pintype "unspecified"))
      (node (ref "INV3") (pin "12") (pinfunction "6Y_12") (pintype "unspecified"))
    )
    (net (code "165") (name "Net-(AND9-1Y)") (class "Default")
      (node (ref "AND9") (pin "3") (pinfunction "1Y_3") (pintype "unspecified"))
      (node (ref "NOR3") (pin "1") (pinfunction "1A_1") (pintype "unspecified"))
    )
    (net (code "166") (name "Net-(AND9-2A)") (class "Default")
      (node (ref "AND9") (pin "4") (pinfunction "2A_4") (pintype "unspecified"))
      (node (ref "INV3") (pin "10") (pinfunction "5Y_10") (pintype "unspecified"))
    )
    (net (code "167") (name "Net-(AND9-2Y)") (class "Default")
      (node (ref "AND9") (pin "6") (pinfunction "2Y_6") (pintype "unspecified"))
      (node (ref "NOR3") (pin "4") (pinfunction "2A_4") (pintype "unspecified"))
    )
    (net (code "168") (name "Net-(INV4-1Y)") (class "Default")
      (node (ref "INV4") (pin "2") (pinfunction "1Y_2") (pintype "unspecified"))
      (node (ref "J14") (pin "3") (pinfunction "3_3") (pintype "input"))
    )
    (net (code "169") (name "Net-(J1-Pad2)") (class "Default")
      (node (ref "J1") (pin "2") (pinfunction "2_2") (pintype "unspecified"))
      (node (ref "SW3") (pin "1") (pinfunction "1_1") (pintype "unspecified"))
    )
    (net (code "170") (name "Net-(J3-Pad1)") (class "Default")
      (node (ref "J3") (pin "1") (pinfunction "1_1") (pintype "unspecified"))
      (node (ref "J4") (pin "2") (pinfunction "2_2") (pintype "unspecified"))
    )
    (net (code "171") (name "Net-(R1-Pad2)") (class "Default")
      (node (ref "R1") (pin "2") (pinfunction "2_2") (pintype "unspecified"))
      (node (ref "SW1") (pin "4") (pinfunction "4_4") (pintype "unspecified"))
      (node (ref "SW2") (pin "1") (pinfunction "1_1") (pintype "unspecified"))
    )
    (net (code "172") (name "Net-(R12-Pad1)") (class "Default")
      (node (ref "R12") (pin "1") (pinfunction "1_1") (pintype "unspecified"))
      (node (ref "R13") (pin "2") (pinfunction "2_2") (pintype "input"))
    )
    (net (code "173") (name "Net-(SW2-Pad3)") (class "Default")
      (node (ref "SW2") (pin "3") (pinfunction "3_3") (pintype "unspecified"))
      (node (ref "SW3") (pin "2") (pinfunction "2_2") (pintype "unspecified"))
    )
    (net (code "174") (name "Net-(U1-CONTROLVOLTAGE)") (class "Default")
      (node (ref "C2") (pin "1") (pinfunction "1_1") (pintype "unspecified"))
      (node (ref "U1") (pin "5") (pinfunction "CONTROLVOLTAGE_5") (pintype "unspecified"))
    )
    (net (code "175") (name "Net-(U1-DISCHARGE)") (class "Default")
      (node (ref "R11") (pin "2") (pinfunction "2_2") (pintype "unspecified"))
      (node (ref "R12") (pin "2") (pinfunction "2_2") (pintype "unspecified"))
      (node (ref "U1") (pin "7") (pinfunction "DISCHARGE_7") (pintype "unspecified"))
    )
    (net (code "176") (name "Net-(U1-OUTPUT)") (class "Default")
      (node (ref "SW3") (pin "3") (pinfunction "3_3") (pintype "unspecified"))
      (node (ref "U1") (pin "3") (pinfunction "OUTPUT_3") (pintype "unspecified"))
    )
    (net (code "177") (name "Net-(U1-THRESHOLD)") (class "Default")
      (node (ref "C3") (pin "1") (pinfunction "1_1") (pintype "unspecified"))
      (node (ref "R13") (pin "1") (pinfunction "1_1") (pintype "input"))
      (node (ref "U1") (pin "2") (pinfunction "TRIGGER_2") (pintype "unspecified"))
      (node (ref "U1") (pin "6") (pinfunction "THRESHOLD_6") (pintype "unspecified"))
    )
    (net (code "178") (name "R1") (class "Default")
      (node (ref "AND11") (pin "12") (pinfunction "1Y_12") (pintype "unspecified"))
      (node (ref "INV4") (pin "9") (pinfunction "4A_9") (pintype "unspecified"))
      (node (ref "NOR2") (pin "1") (pinfunction "1A_1") (pintype "unspecified"))
    )
    (net (code "179") (name "R1_INV") (class "Default")
      (node (ref "AND9") (pin "2") (pinfunction "1B_2") (pintype "unspecified"))
      (node (ref "INV4") (pin "8") (pinfunction "4Y_8") (pintype "unspecified"))
    )
    (net (code "180") (name "R2") (class "Default")
      (node (ref "AND11") (pin "6") (pinfunction "2Y_6") (pintype "unspecified"))
      (node (ref "INV4") (pin "11") (pinfunction "5A_11") (pintype "unspecified"))
      (node (ref "NOR2") (pin "2") (pinfunction "1B_2") (pintype "unspecified"))
    )
    (net (code "181") (name "R2_INV") (class "Default")
      (node (ref "AND9") (pin "5") (pinfunction "2B_5") (pintype "unspecified"))
      (node (ref "INV4") (pin "10") (pinfunction "5Y_10") (pintype "unspecified"))
    )
    (net (code "182") (name "R3") (class "Default")
      (node (ref "AND11") (pin "8") (pinfunction "3Y_8") (pintype "unspecified"))
      (node (ref "AND5") (pin "1") (pinfunction "1A_1") (pintype "unspecified"))
      (node (ref "NOR2") (pin "3") (pinfunction "1C_3") (pintype "unspecified"))
    )
    (net (code "183") (name "R4") (class "Default")
      (node (ref "AND12") (pin "12") (pinfunction "1Y_12") (pintype "unspecified"))
      (node (ref "AND5") (pin "4") (pinfunction "2A_4") (pintype "unspecified"))
      (node (ref "NOR2") (pin "12") (pinfunction "1D_12") (pintype "unspecified"))
    )
    (net (code "184") (name "R7") (class "Default")
      (node (ref "AND12") (pin "11") (pinfunction "3C_11") (pintype "unspecified"))
      (node (ref "AND12") (pin "6") (pinfunction "2Y_6") (pintype "unspecified"))
      (node (ref "NOR2") (pin "13") (pinfunction "1E_13") (pintype "unspecified"))
    )
    (net (code "185") (name "RAM_EN") (class "Default")
      (node (ref "INV4") (pin "3") (pinfunction "2A_3") (pintype "unspecified"))
      (node (ref "NOR2") (pin "5") (pinfunction "1Y_5") (pintype "unspecified"))
    )
    (net (code "186") (name "RAM_EN_INV") (class "Default")
      (node (ref "INV4") (pin "4") (pinfunction "2Y_4") (pintype "unspecified"))
      (node (ref "RAM1") (pin "20") (pinfunction "CE#_20") (pintype "unspecified"))
    )
    (net (code "187") (name "RAM_WE") (class "Default")
      (node (ref "AND9") (pin "8") (pinfunction "3Y_8") (pintype "unspecified"))
      (node (ref "INV4") (pin "5") (pinfunction "3A_5") (pintype "unspecified"))
    )
    (net (code "188") (name "RAM_WE_INV") (class "Default")
      (node (ref "INV4") (pin "6") (pinfunction "3Y_6") (pintype "unspecified"))
      (node (ref "NOR3") (pin "2") (pinfunction "1B_2") (pintype "unspecified"))
      (node (ref "NOR3") (pin "8") (pinfunction "2B_8") (pintype "unspecified"))
      (node (ref "RAM1") (pin "27") (pinfunction "WE#_27") (pintype "unspecified"))
    )
    (net (code "189") (name "READ_A") (class "Default")
      (node (ref "AND5") (pin "8") (pinfunction "3Y_8") (pintype "unspecified"))
      (node (ref "REG_A") (pin "11") (pinfunction "CLK_11") (pintype "unspecified"))
    )
    (net (code "190") (name "READ_B") (class "Default")
      (node (ref "AND5") (pin "11") (pinfunction "4Y_11") (pintype "unspecified"))
      (node (ref "REG_B") (pin "11") (pinfunction "CLK_11") (pintype "unspecified"))
    )
    (net (code "191") (name "READ_IR_O") (class "Default")
      (node (ref "NOR3") (pin "5") (pinfunction "1Y_5") (pintype "unspecified"))
      (node (ref "REG_IRO") (pin "11") (pinfunction "CLK_11") (pintype "unspecified"))
    )
    (net (code "192") (name "READ_RP") (class "Default")
      (node (ref "AND6") (pin "3") (pinfunction "1Y_3") (pintype "unspecified"))
      (node (ref "REG_RP") (pin "11") (pinfunction "CLK_11") (pintype "unspecified"))
    )
    (net (code "193") (name "RP0") (class "Default")
      (node (ref "AND6") (pin "4") (pinfunction "2A_4") (pintype "unspecified"))
      (node (ref "BUF11") (pin "2") (pinfunction "1A_2") (pintype "unspecified"))
      (node (ref "J18") (pin "10") (pinfunction "10_10") (pintype "unspecified"))
      (node (ref "RAM1") (pin "10") (pinfunction "A0_10") (pintype "unspecified"))
      (node (ref "REG_RP") (pin "2") (pinfunction "1Q_2") (pintype "unspecified"))
    )
    (net (code "194") (name "RP1") (class "Default")
      (node (ref "AND6") (pin "9") (pinfunction "3A_9") (pintype "unspecified"))
      (node (ref "BUF11") (pin "5") (pinfunction "2A_5") (pintype "unspecified"))
      (node (ref "J18") (pin "9") (pinfunction "9_9") (pintype "unspecified"))
      (node (ref "RAM1") (pin "9") (pinfunction "A1_9") (pintype "unspecified"))
      (node (ref "REG_RP") (pin "5") (pinfunction "2Q_5") (pintype "unspecified"))
    )
    (net (code "195") (name "RP2") (class "Default")
      (node (ref "AND6") (pin "12") (pinfunction "4A_12") (pintype "unspecified"))
      (node (ref "BUF11") (pin "9") (pinfunction "3A_9") (pintype "unspecified"))
      (node (ref "J18") (pin "8") (pinfunction "8_8") (pintype "unspecified"))
      (node (ref "RAM1") (pin "8") (pinfunction "A2_8") (pintype "unspecified"))
      (node (ref "REG_RP") (pin "6") (pinfunction "3Q_6") (pintype "unspecified"))
    )
    (net (code "196") (name "RP3") (class "Default")
      (node (ref "BUF11") (pin "12") (pinfunction "4A_12") (pintype "unspecified"))
      (node (ref "J18") (pin "7") (pinfunction "7_7") (pintype "unspecified"))
      (node (ref "NOR1") (pin "1") (pinfunction "1A_1") (pintype "unspecified"))
      (node (ref "RAM1") (pin "7") (pinfunction "A3_7") (pintype "unspecified"))
      (node (ref "REG_RP") (pin "9") (pinfunction "4Q_9") (pintype "unspecified"))
    )
    (net (code "197") (name "RP4") (class "Default")
      (node (ref "BUF12") (pin "2") (pinfunction "1A_2") (pintype "unspecified"))
      (node (ref "J18") (pin "6") (pinfunction "6_6") (pintype "unspecified"))
      (node (ref "NOR1") (pin "2") (pinfunction "1B_2") (pintype "unspecified"))
      (node (ref "RAM1") (pin "6") (pinfunction "A4_6") (pintype "unspecified"))
      (node (ref "REG_RP") (pin "12") (pinfunction "5Q_12") (pintype "unspecified"))
    )
    (net (code "198") (name "RP5") (class "Default")
      (node (ref "BUF12") (pin "5") (pinfunction "2A_5") (pintype "unspecified"))
      (node (ref "J18") (pin "5") (pinfunction "5_5") (pintype "unspecified"))
      (node (ref "NOR1") (pin "3") (pinfunction "1C_3") (pintype "unspecified"))
      (node (ref "RAM1") (pin "5") (pinfunction "A5_5") (pintype "unspecified"))
      (node (ref "REG_RP") (pin "15") (pinfunction "6Q_15") (pintype "unspecified"))
    )
    (net (code "199") (name "RP6") (class "Default")
      (node (ref "BUF12") (pin "9") (pinfunction "3A_9") (pintype "unspecified"))
      (node (ref "J18") (pin "4") (pinfunction "4_4") (pintype "unspecified"))
      (node (ref "NOR1") (pin "12") (pinfunction "1D_12") (pintype "unspecified"))
      (node (ref "RAM1") (pin "4") (pinfunction "A6_4") (pintype "unspecified"))
      (node (ref "REG_RP") (pin "16") (pinfunction "7Q_16") (pintype "unspecified"))
    )
    (net (code "200") (name "RP7") (class "Default")
      (node (ref "BUF12") (pin "12") (pinfunction "4A_12") (pintype "unspecified"))
      (node (ref "J18") (pin "3") (pinfunction "3_3") (pintype "unspecified"))
      (node (ref "NOR1") (pin "13") (pinfunction "1E_13") (pintype "unspecified"))
      (node (ref "RAM1") (pin "3") (pinfunction "A7_3") (pintype "unspecified"))
      (node (ref "REG_RP") (pin "19") (pinfunction "8Q_19") (pintype "unspecified"))
    )
    (net (code "201") (name "RST") (class "Default")
      (node (ref "J7") (pin "2") (pinfunction "2_2") (pintype "unspecified"))
      (node (ref "NOR2") (pin "8") (pinfunction "2B_8") (pintype "unspecified"))
      (node (ref "R10") (pin "2") (pinfunction "2_2") (pintype "unspecified"))
      (node (ref "SW4") (pin "4") (pinfunction "4_4") (pintype "unspecified"))
    )
    (net (code "202") (name "VCC") (class "Default")
      (node (ref "ADD1") (pin "16") (pinfunction "VCC_16") (pintype "unspecified"))
      (node (ref "ADD2") (pin "16") (pinfunction "VCC_16") (pintype "unspecified"))
      (node (ref "AND1") (pin "14") (pinfunction "VCC_14") (pintype "unspecified"))
      (node (ref "AND1") (pin "2") (pinfunction "1B_2") (pintype "unspecified"))
      (node (ref "AND11") (pin "14") (pinfunction "VCC_14") (pintype "unspecified"))
      (node (ref "AND12") (pin "14") (pinfunction "VCC_14") (pintype "unspecified"))
      (node (ref "AND2") (pin "14") (pinfunction "VCC_14") (pintype "unspecified"))
      (node (ref "AND3") (pin "14") (pinfunction "VCC_14") (pintype "unspecified"))
      (node (ref "AND4") (pin "14") (pinfunction "VCC_14") (pintype "unspecified"))
      (node (ref "AND5") (pin "14") (pinfunction "VCC_14") (pintype "unspecified"))
      (node (ref "AND6") (pin "14") (pinfunction "VCC_14") (pintype "unspecified"))
      (node (ref "AND7") (pin "14") (pinfunction "VCC_14") (pintype "unspecified"))
      (node (ref "AND8") (pin "14") (pinfunction "VCC_14") (pintype "unspecified"))
      (node (ref "AND8") (pin "2") (pinfunction "1B_2") (pintype "unspecified"))
      (node (ref "AND9") (pin "14") (pinfunction "VCC_14") (pintype "unspecified"))
      (node (ref "BUF1") (pin "14") (pinfunction "VCC_14") (pintype "unspecified"))
      (node (ref "BUF10") (pin "14") (pinfunction "VCC_14") (pintype "unspecified"))
      (node (ref "BUF11") (pin "14") (pinfunction "VCC_14") (pintype "unspecified"))
      (node (ref "BUF12") (pin "14") (pinfunction "VCC_14") (pintype "unspecified"))
      (node (ref "BUF13") (pin "14") (pinfunction "VCC_14") (pintype "unspecified"))
      (node (ref "BUF14") (pin "14") (pinfunction "VCC_14") (pintype "unspecified"))
      (node (ref "BUF15") (pin "14") (pinfunction "VCC_14") (pintype "unspecified"))
      (node (ref "BUF16") (pin "14") (pinfunction "VCC_14") (pintype "unspecified"))
      (node (ref "BUF2") (pin "14") (pinfunction "VCC_14") (pintype "unspecified"))
      (node (ref "BUF3") (pin "14") (pinfunction "VCC_14") (pintype "unspecified"))
      (node (ref "BUF4") (pin "14") (pinfunction "VCC_14") (pintype "unspecified"))
      (node (ref "BUF5") (pin "14") (pinfunction "VCC_14") (pintype "unspecified"))
      (node (ref "BUF6") (pin "14") (pinfunction "VCC_14") (pintype "unspecified"))
      (node (ref "BUF7") (pin "14") (pinfunction "VCC_14") (pintype "unspecified"))
      (node (ref "BUF8") (pin "14") (pinfunction "VCC_14") (pintype "unspecified"))
      (node (ref "BUF9") (pin "14") (pinfunction "VCC_14") (pintype "unspecified"))
      (node (ref "C1") (pin "2") (pinfunction "2_2") (pintype "unspecified"))
      (node (ref "C10") (pin "2") (pinfunction "2_2") (pintype "unspecified"))
      (node (ref "C102") (pin "2") (pinfunction "2_2") (pintype "unspecified"))
      (node (ref "C103") (pin "2") (pinfunction "2_2") (pintype "unspecified"))
      (node (ref "C104") (pin "2") (pinfunction "2_2") (pintype "unspecified"))
      (node (ref "C105") (pin "2") (pinfunction "2_2") (pintype "unspecified"))
      (node (ref "C106") (pin "2") (pinfunction "2_2") (pintype "unspecified"))
      (node (ref "C107") (pin "2") (pinfunction "2_2") (pintype "unspecified"))
      (node (ref "C108") (pin "2") (pinfunction "2_2") (pintype "unspecified"))
      (node (ref "C109") (pin "2") (pinfunction "2_2") (pintype "unspecified"))
      (node (ref "C11") (pin "2") (pinfunction "2_2") (pintype "unspecified"))
      (node (ref "C110") (pin "2") (pinfunction "2_2") (pintype "unspecified"))
      (node (ref "C111") (pin "2") (pinfunction "2_2") (pintype "unspecified"))
      (node (ref "C112") (pin "2") (pinfunction "2_2") (pintype "unspecified"))
      (node (ref "C12") (pin "2") (pinfunction "2_2") (pintype "unspecified"))
      (node (ref "C13") (pin "2") (pinfunction "2_2") (pintype "unspecified"))
      (node (ref "C14") (pin "2") (pinfunction "2_2") (pintype "unspecified"))
      (node (ref "C15") (pin "1") (pinfunction "1_1") (pintype "input"))
      (node (ref "C4") (pin "2") (pinfunction "2_2") (pintype "unspecified"))
      (node (ref "C5") (pin "2") (pinfunction "2_2") (pintype "unspecified"))
      (node (ref "C58") (pin "2") (pinfunction "2_2") (pintype "unspecified"))
      (node (ref "C59") (pin "2") (pinfunction "2_2") (pintype "unspecified"))
      (node (ref "C6") (pin "2") (pinfunction "2_2") (pintype "unspecified"))
      (node (ref "C60") (pin "2") (pinfunction "2_2") (pintype "unspecified"))
      (node (ref "C61") (pin "2") (pinfunction "2_2") (pintype "unspecified"))
      (node (ref "C62") (pin "2") (pinfunction "2_2") (pintype "unspecified"))
      (node (ref "C63") (pin "2") (pinfunction "2_2") (pintype "unspecified"))
      (node (ref "C64") (pin "2") (pinfunction "2_2") (pintype "unspecified"))
      (node (ref "C7") (pin "2") (pinfunction "2_2") (pintype "unspecified"))
      (node (ref "C70") (pin "2") (pinfunction "2_2") (pintype "unspecified"))
      (node (ref "C71") (pin "2") (pinfunction "2_2") (pintype "unspecified"))
      (node (ref "C72") (pin "2") (pinfunction "2_2") (pintype "unspecified"))
      (node (ref "C73") (pin "2") (pinfunction "2_2") (pintype "unspecified"))
      (node (ref "C74") (pin "2") (pinfunction "2_2") (pintype "unspecified"))
      (node (ref "C75") (pin "2") (pinfunction "2_2") (pintype "unspecified"))
      (node (ref "C76") (pin "2") (pinfunction "2_2") (pintype "unspecified"))
      (node (ref "C77") (pin "2") (pinfunction "2_2") (pintype "unspecified"))
      (node (ref "C78") (pin "2") (pinfunction "2_2") (pintype "unspecified"))
      (node (ref "C79") (pin "2") (pinfunction "2_2") (pintype "unspecified"))
      (node (ref "C8") (pin "2") (pinfunction "2_2") (pintype "unspecified"))
      (node (ref "C85") (pin "2") (pinfunction "2_2") (pintype "unspecified"))
      (node (ref "C86") (pin "2") (pinfunction "2_2") (pintype "unspecified"))
      (node (ref "C87") (pin "2") (pinfunction "2_2") (pintype "unspecified"))
      (node (ref "C88") (pin "2") (pinfunction "2_2") (pintype "unspecified"))
      (node (ref "C89") (pin "2") (pinfunction "2_2") (pintype "unspecified"))
      (node (ref "C9") (pin "2") (pinfunction "2_2") (pintype "unspecified"))
      (node (ref "C90") (pin "2") (pinfunction "2_2") (pintype "unspecified"))
      (node (ref "C91") (pin "2") (pinfunction "2_2") (pintype "unspecified"))
      (node (ref "C92") (pin "2") (pinfunction "2_2") (pintype "unspecified"))
      (node (ref "C93") (pin "2") (pinfunction "2_2") (pintype "unspecified"))
      (node (ref "C94") (pin "2") (pinfunction "2_2") (pintype "unspecified"))
      (node (ref "C95") (pin "2") (pinfunction "2_2") (pintype "unspecified"))
      (node (ref "C96") (pin "2") (pinfunction "2_2") (pintype "unspecified"))
      (node (ref "INV1") (pin "14") (pinfunction "VCC_14") (pintype "unspecified"))
      (node (ref "INV2") (pin "14") (pinfunction "VCC_14") (pintype "unspecified"))
      (node (ref "INV3") (pin "14") (pinfunction "VCC_14") (pintype "unspecified"))
      (node (ref "INV4") (pin "14") (pinfunction "VCC_14") (pintype "unspecified"))
      (node (ref "J10") (pin "2") (pinfunction "2_2") (pintype "unspecified"))
      (node (ref "J11") (pin "2") (pinfunction "2_2") (pintype "unspecified"))
      (node (ref "J12") (pin "2") (pinfunction "2_2") (pintype "unspecified"))
      (node (ref "J13") (pin "2") (pinfunction "2_2") (pintype "unspecified"))
      (node (ref "J16") (pin "2") (pinfunction "2_2") (pintype "unspecified"))
      (node (ref "J17") (pin "2") (pinfunction "2_2") (pintype "unspecified"))
      (node (ref "J18") (pin "2") (pinfunction "2_2") (pintype "unspecified"))
      (node (ref "J2") (pin "2") (pinfunction "2_2") (pintype "unspecified"))
      (node (ref "J4") (pin "1") (pinfunction "1_1") (pintype "unspecified"))
      (node (ref "J5") (pin "2") (pinfunction "2_2") (pintype "unspecified"))
      (node (ref "J9") (pin "2") (pinfunction "2_2") (pintype "unspecified"))
      (node (ref "NOR1") (pin "14") (pinfunction "VCC_14") (pintype "unspecified"))
      (node (ref "NOR2") (pin "14") (pinfunction "VCC_14") (pintype "unspecified"))
      (node (ref "NOR3") (pin "14") (pinfunction "VCC_14") (pintype "unspecified"))
      (node (ref "R11") (pin "1") (pinfunction "1_1") (pintype "unspecified"))
      (node (ref "RAM1") (pin "28") (pinfunction "VCC_28") (pintype "unspecified"))
      (node (ref "REG1") (pin "20") (pinfunction "VCC_20") (pintype "unspecified"))
      (node (ref "REG2") (pin "20") (pinfunction "VCC_20") (pintype "unspecified"))
      (node (ref "REG_A") (pin "20") (pinfunction "VCC_20") (pintype "unspecified"))
      (node (ref "REG_B") (pin "20") (pinfunction "VCC_20") (pintype "unspecified"))
      (node (ref "REG_IRO") (pin "20") (pinfunction "VCC_20") (pintype "unspecified"))
      (node (ref "REG_RP") (pin "20") (pinfunction "VCC_20") (pintype "unspecified"))
      (node (ref "ROM1") (pin "31") (pinfunction "WE#_31") (pintype "unspecified"))
      (node (ref "ROM1") (pin "32") (pinfunction "VDD_32") (pintype "unspecified"))
      (node (ref "ROM2") (pin "31") (pinfunction "WE#_31") (pintype "unspecified"))
      (node (ref "ROM2") (pin "32") (pinfunction "VDD_32") (pintype "unspecified"))
      (node (ref "SW1") (pin "5") (pinfunction "5_5") (pintype "unspecified"))
      (node (ref "SW4") (pin "5") (pinfunction "5_5") (pintype "unspecified"))
      (node (ref "U1") (pin "4") (pinfunction "RESET_4") (pintype "unspecified"))
      (node (ref "U1") (pin "8") (pinfunction "VCC_8") (pintype "unspecified"))
      (node (ref "XOR1") (pin "14") (pinfunction "VCC_14") (pintype "unspecified"))
      (node (ref "XOR1") (pin "2") (pinfunction "1B_2") (pintype "unspecified"))
      (node (ref "XOR2") (pin "14") (pinfunction "VCC_14") (pintype "unspecified"))
      (node (ref "XOR3") (pin "14") (pinfunction "VCC_14") (pintype "unspecified"))
      (node (ref "XOR4") (pin "14") (pinfunction "VCC_14") (pintype "unspecified"))
      (node (ref "XOR5") (pin "14") (pinfunction "VCC_14") (pintype "unspecified"))
      (node (ref "XOR6") (pin "14") (pinfunction "VCC_14") (pintype "unspecified"))
      (node (ref "XOR6") (pin "2") (pinfunction "1B_2") (pintype "unspecified"))
    )
    (net (code "203") (name "unconnected-(AND9-4A-Pad12)") (class "Default")
      (node (ref "AND9") (pin "12") (pinfunction "4A_12") (pintype "unspecified+no_connect"))
    )
    (net (code "204") (name "unconnected-(AND9-4B-Pad13)") (class "Default")
      (node (ref "AND9") (pin "13") (pinfunction "4B_13") (pintype "unspecified+no_connect"))
    )
    (net (code "205") (name "unconnected-(AND9-4Y-Pad11)") (class "Default")
      (node (ref "AND9") (pin "11") (pinfunction "4Y_11") (pintype "unspecified+no_connect"))
    )
    (net (code "206") (name "unconnected-(INV2-3A-Pad5)") (class "Default")
      (node (ref "INV2") (pin "5") (pinfunction "3A_5") (pintype "unspecified+no_connect"))
    )
    (net (code "207") (name "unconnected-(INV2-3Y-Pad6)") (class "Default")
      (node (ref "INV2") (pin "6") (pinfunction "3Y_6") (pintype "unspecified+no_connect"))
    )
    (net (code "208") (name "unconnected-(INV2-4A-Pad9)") (class "Default")
      (node (ref "INV2") (pin "9") (pinfunction "4A_9") (pintype "unspecified+no_connect"))
    )
    (net (code "209") (name "unconnected-(INV2-4Y-Pad8)") (class "Default")
      (node (ref "INV2") (pin "8") (pinfunction "4Y_8") (pintype "unspecified+no_connect"))
    )
    (net (code "210") (name "unconnected-(INV2-5A-Pad11)") (class "Default")
      (node (ref "INV2") (pin "11") (pinfunction "5A_11") (pintype "unspecified+no_connect"))
    )
    (net (code "211") (name "unconnected-(INV2-5Y-Pad10)") (class "Default")
      (node (ref "INV2") (pin "10") (pinfunction "5Y_10") (pintype "unspecified+no_connect"))
    )
    (net (code "212") (name "unconnected-(INV2-6A-Pad13)") (class "Default")
      (node (ref "INV2") (pin "13") (pinfunction "6A_13") (pintype "unspecified+no_connect"))
    )
    (net (code "213") (name "unconnected-(INV2-6Y-Pad12)") (class "Default")
      (node (ref "INV2") (pin "12") (pinfunction "6Y_12") (pintype "unspecified+no_connect"))
    )
    (net (code "214") (name "unconnected-(INV3-4A-Pad9)") (class "Default")
      (node (ref "INV3") (pin "9") (pinfunction "4A_9") (pintype "unspecified+no_connect"))
    )
    (net (code "215") (name "unconnected-(INV3-4Y-Pad8)") (class "Default")
      (node (ref "INV3") (pin "8") (pinfunction "4Y_8") (pintype "unspecified+no_connect"))
    )
    (net (code "216") (name "unconnected-(J2-Pad3)") (class "Default")
      (node (ref "J2") (pin "3") (pinfunction "3_3") (pintype "unspecified+no_connect"))
    )
    (net (code "217") (name "unconnected-(J2-Pad4)") (class "Default")
      (node (ref "J2") (pin "4") (pinfunction "4_4") (pintype "unspecified+no_connect"))
    )
    (net (code "218") (name "unconnected-(NOR1-2E-Pad11)") (class "Default")
      (node (ref "NOR1") (pin "11") (pinfunction "2E_11") (pintype "unspecified+no_connect"))
    )
    (net (code "219") (name "unconnected-(NOR2-2C-Pad9)") (class "Default")
      (node (ref "NOR2") (pin "9") (pinfunction "2C_9") (pintype "unspecified+no_connect"))
    )
    (net (code "220") (name "unconnected-(NOR2-2D-Pad10)") (class "Default")
      (node (ref "NOR2") (pin "10") (pinfunction "2D_10") (pintype "unspecified+no_connect"))
    )
    (net (code "221") (name "unconnected-(NOR2-2E-Pad11)") (class "Default")
      (node (ref "NOR2") (pin "11") (pinfunction "2E_11") (pintype "unspecified+no_connect"))
    )
    (net (code "222") (name "unconnected-(NOR3-1C-Pad3)") (class "Default")
      (node (ref "NOR3") (pin "3") (pinfunction "1C_3") (pintype "unspecified+no_connect"))
    )
    (net (code "223") (name "unconnected-(NOR3-1D-Pad12)") (class "Default")
      (node (ref "NOR3") (pin "12") (pinfunction "1D_12") (pintype "unspecified+no_connect"))
    )
    (net (code "224") (name "unconnected-(NOR3-1E-Pad13)") (class "Default")
      (node (ref "NOR3") (pin "13") (pinfunction "1E_13") (pintype "unspecified+no_connect"))
    )
    (net (code "225") (name "unconnected-(NOR3-2C-Pad9)") (class "Default")
      (node (ref "NOR3") (pin "9") (pinfunction "2C_9") (pintype "unspecified+no_connect"))
    )
    (net (code "226") (name "unconnected-(NOR3-2D-Pad10)") (class "Default")
      (node (ref "NOR3") (pin "10") (pinfunction "2D_10") (pintype "unspecified+no_connect"))
    )
    (net (code "227") (name "unconnected-(NOR3-2E-Pad11)") (class "Default")
      (node (ref "NOR3") (pin "11") (pinfunction "2E_11") (pintype "unspecified+no_connect"))
    )
    (net (code "228") (name "unconnected-(R13-Pad3)") (class "Default")
      (node (ref "R13") (pin "3") (pinfunction "3_3") (pintype "input+no_connect"))
    )
    (net (code "229") (name "unconnected-(RAM1-A8-Pad25)") (class "Default")
      (node (ref "RAM1") (pin "25") (pinfunction "A8_25") (pintype "unspecified+no_connect"))
    )
    (net (code "230") (name "unconnected-(RAM1-A9-Pad24)") (class "Default")
      (node (ref "RAM1") (pin "24") (pinfunction "A9_24") (pintype "unspecified+no_connect"))
    )
    (net (code "231") (name "unconnected-(RAM1-A10-Pad21)") (class "Default")
      (node (ref "RAM1") (pin "21") (pinfunction "A10_21") (pintype "unspecified+no_connect"))
    )
    (net (code "232") (name "unconnected-(RAM1-A11-Pad23)") (class "Default")
      (node (ref "RAM1") (pin "23") (pinfunction "A11_23") (pintype "unspecified+no_connect"))
    )
    (net (code "233") (name "unconnected-(RAM1-A12-Pad2)") (class "Default")
      (node (ref "RAM1") (pin "2") (pinfunction "A12_2") (pintype "unspecified+no_connect"))
    )
    (net (code "234") (name "unconnected-(RAM1-A13-Pad26)") (class "Default")
      (node (ref "RAM1") (pin "26") (pinfunction "A13_26") (pintype "unspecified+no_connect"))
    )
    (net (code "235") (name "unconnected-(RAM1-A14-Pad1)") (class "Default")
      (node (ref "RAM1") (pin "1") (pinfunction "A14_1") (pintype "unspecified+no_connect"))
    )
    (net (code "236") (name "unconnected-(ROM1-A16-Pad2)") (class "Default")
      (node (ref "ROM1") (pin "2") (pinfunction "A16_2") (pintype "unspecified+no_connect"))
    )
    (net (code "237") (name "unconnected-(ROM1-A17-Pad30)") (class "Default")
      (node (ref "ROM1") (pin "30") (pinfunction "A17_30") (pintype "unspecified+no_connect"))
    )
    (net (code "238") (name "unconnected-(ROM1-NC-Pad1)") (class "Default")
      (node (ref "ROM1") (pin "1") (pinfunction "NC_1") (pintype "unspecified+no_connect"))
    )
    (net (code "239") (name "unconnected-(ROM2-A16-Pad2)") (class "Default")
      (node (ref "ROM2") (pin "2") (pinfunction "A16_2") (pintype "unspecified+no_connect"))
    )
    (net (code "240") (name "unconnected-(ROM2-A17-Pad30)") (class "Default")
      (node (ref "ROM2") (pin "30") (pinfunction "A17_30") (pintype "unspecified+no_connect"))
    )
    (net (code "241") (name "unconnected-(ROM2-NC-Pad1)") (class "Default")
      (node (ref "ROM2") (pin "1") (pinfunction "NC_1") (pintype "unspecified+no_connect"))
    )
    (net (code "242") (name "unconnected-(SW1-Pad1)") (class "Default")
      (node (ref "SW1") (pin "1") (pinfunction "1_1") (pintype "unspecified+no_connect"))
    )
    (net (code "243") (name "unconnected-(SW1-Pad2)") (class "Default")
      (node (ref "SW1") (pin "2") (pinfunction "2_2") (pintype "unspecified+no_connect"))
    )
    (net (code "244") (name "unconnected-(SW1-Pad3)") (class "Default")
      (node (ref "SW1") (pin "3") (pinfunction "3_3") (pintype "unspecified+no_connect"))
    )
    (net (code "245") (name "unconnected-(SW1-Pad6)") (class "Default")
      (node (ref "SW1") (pin "6") (pinfunction "6_6") (pintype "unspecified+no_connect"))
    )
    (net (code "246") (name "unconnected-(SW2-Pad4)") (class "Default")
      (node (ref "SW2") (pin "4") (pinfunction "4_4") (pintype "unspecified+no_connect"))
    )
    (net (code "247") (name "unconnected-(SW2-Pad5)") (class "Default")
      (node (ref "SW2") (pin "5") (pinfunction "5_5") (pintype "unspecified+no_connect"))
    )
    (net (code "248") (name "unconnected-(SW3-Pad4)") (class "Default")
      (node (ref "SW3") (pin "4") (pinfunction "4_4") (pintype "unspecified+no_connect"))
    )
    (net (code "249") (name "unconnected-(SW3-Pad5)") (class "Default")
      (node (ref "SW3") (pin "5") (pinfunction "5_5") (pintype "unspecified+no_connect"))
    )
    (net (code "250") (name "unconnected-(SW4-Pad1)") (class "Default")
      (node (ref "SW4") (pin "1") (pinfunction "1_1") (pintype "unspecified+no_connect"))
    )
    (net (code "251") (name "unconnected-(SW4-Pad2)") (class "Default")
      (node (ref "SW4") (pin "2") (pinfunction "2_2") (pintype "unspecified+no_connect"))
    )
    (net (code "252") (name "unconnected-(SW4-Pad3)") (class "Default")
      (node (ref "SW4") (pin "3") (pinfunction "3_3") (pintype "unspecified+no_connect"))
    )
    (net (code "253") (name "unconnected-(SW4-Pad6)") (class "Default")
      (node (ref "SW4") (pin "6") (pinfunction "6_6") (pintype "unspecified+no_connect"))
    )
  )
)
